# S140039_EMS_3HP_DS.net
KiCad netlist of a schematic drawn in EAGLE
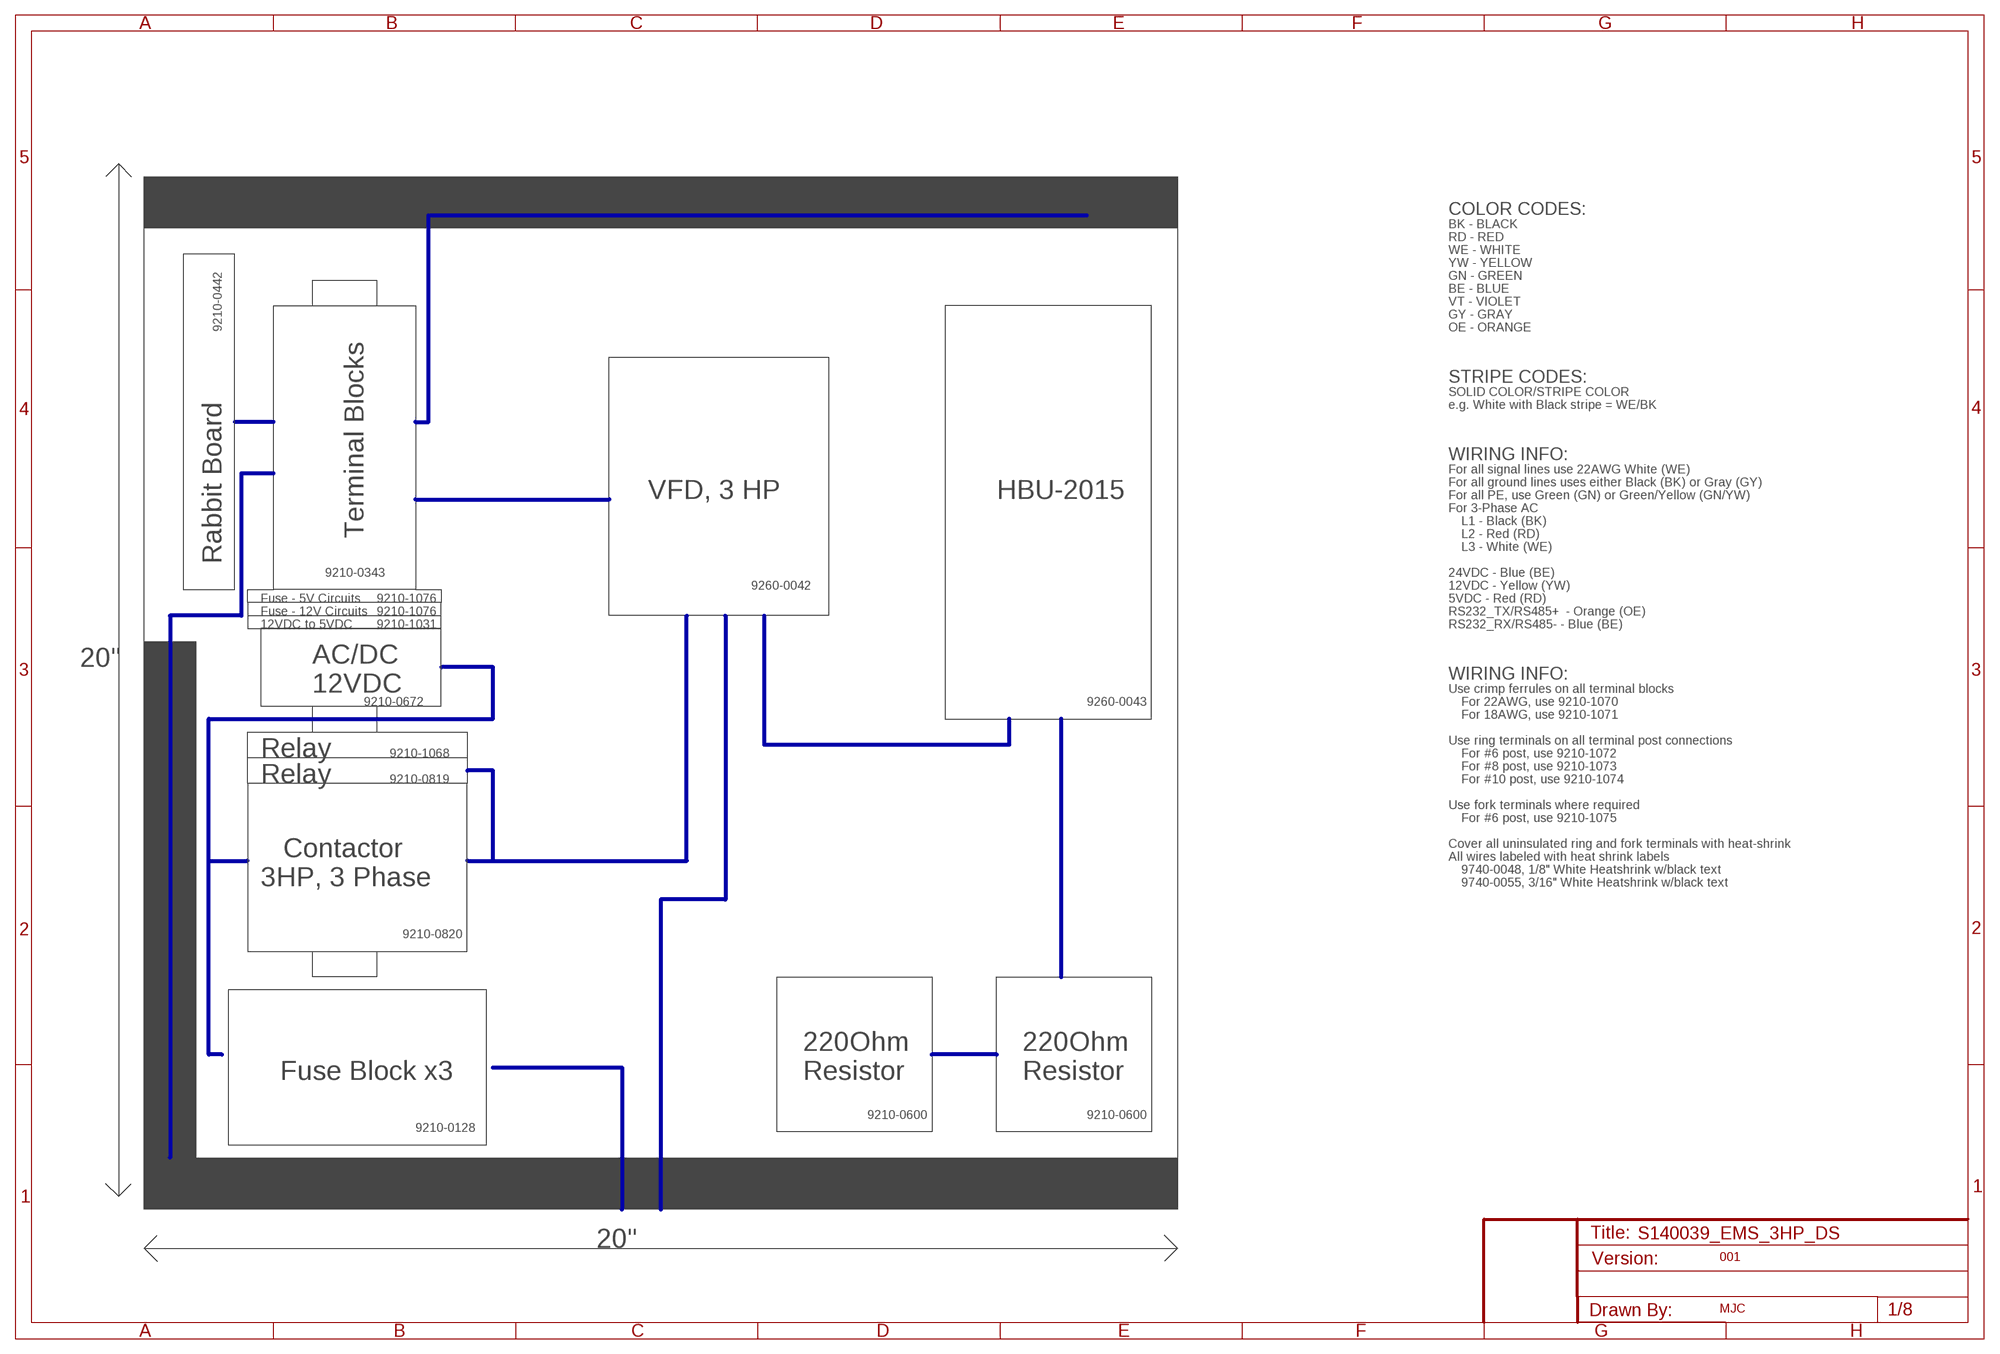
[diagram p0: schematic, sheet 1]
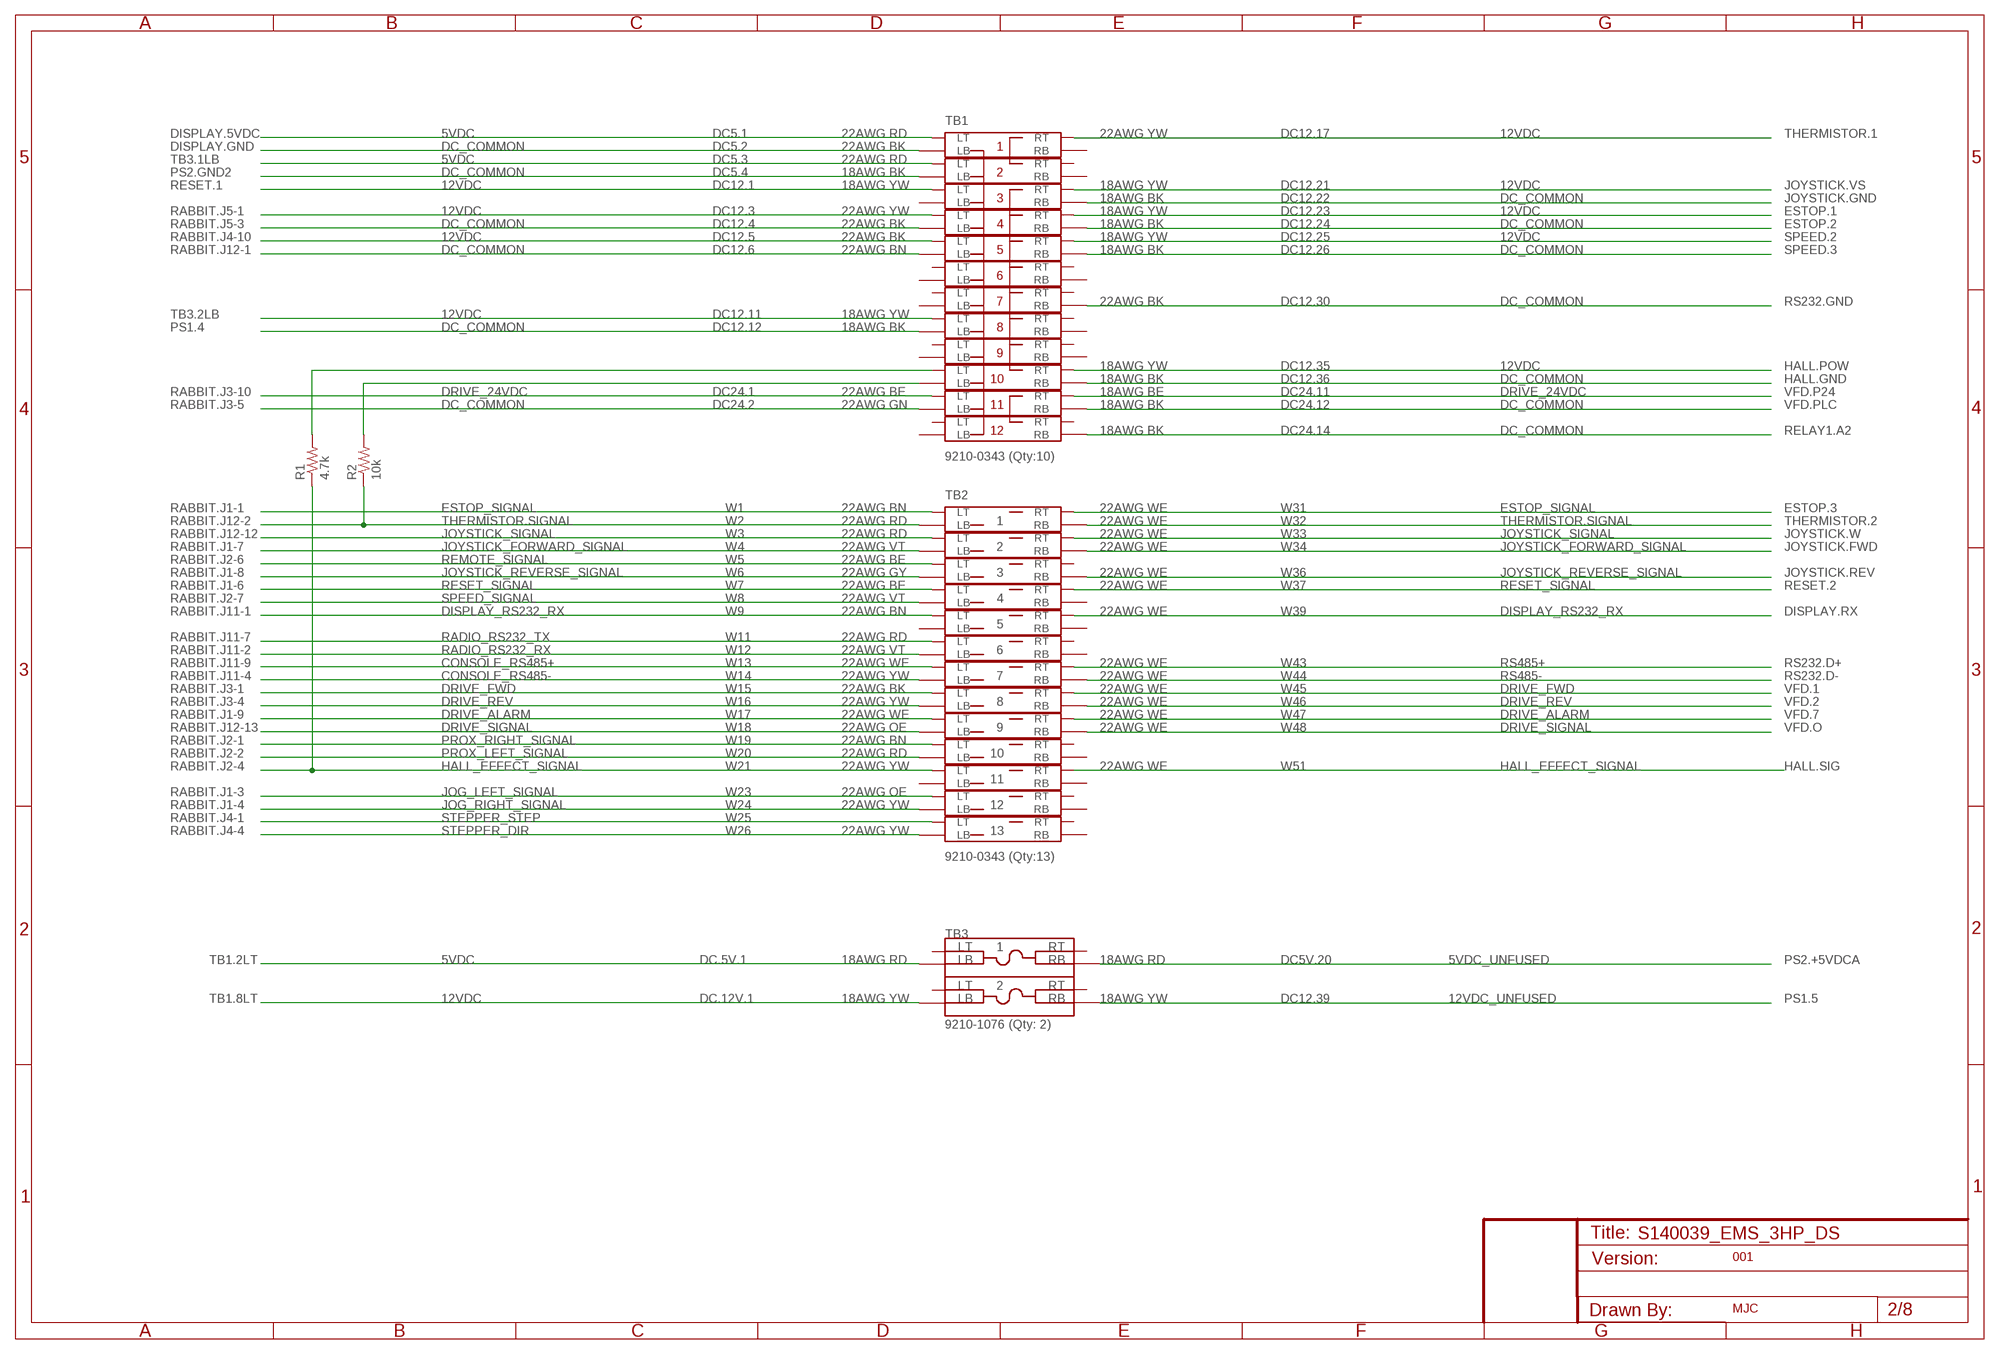
[diagram p1: schematic, sheet 2]
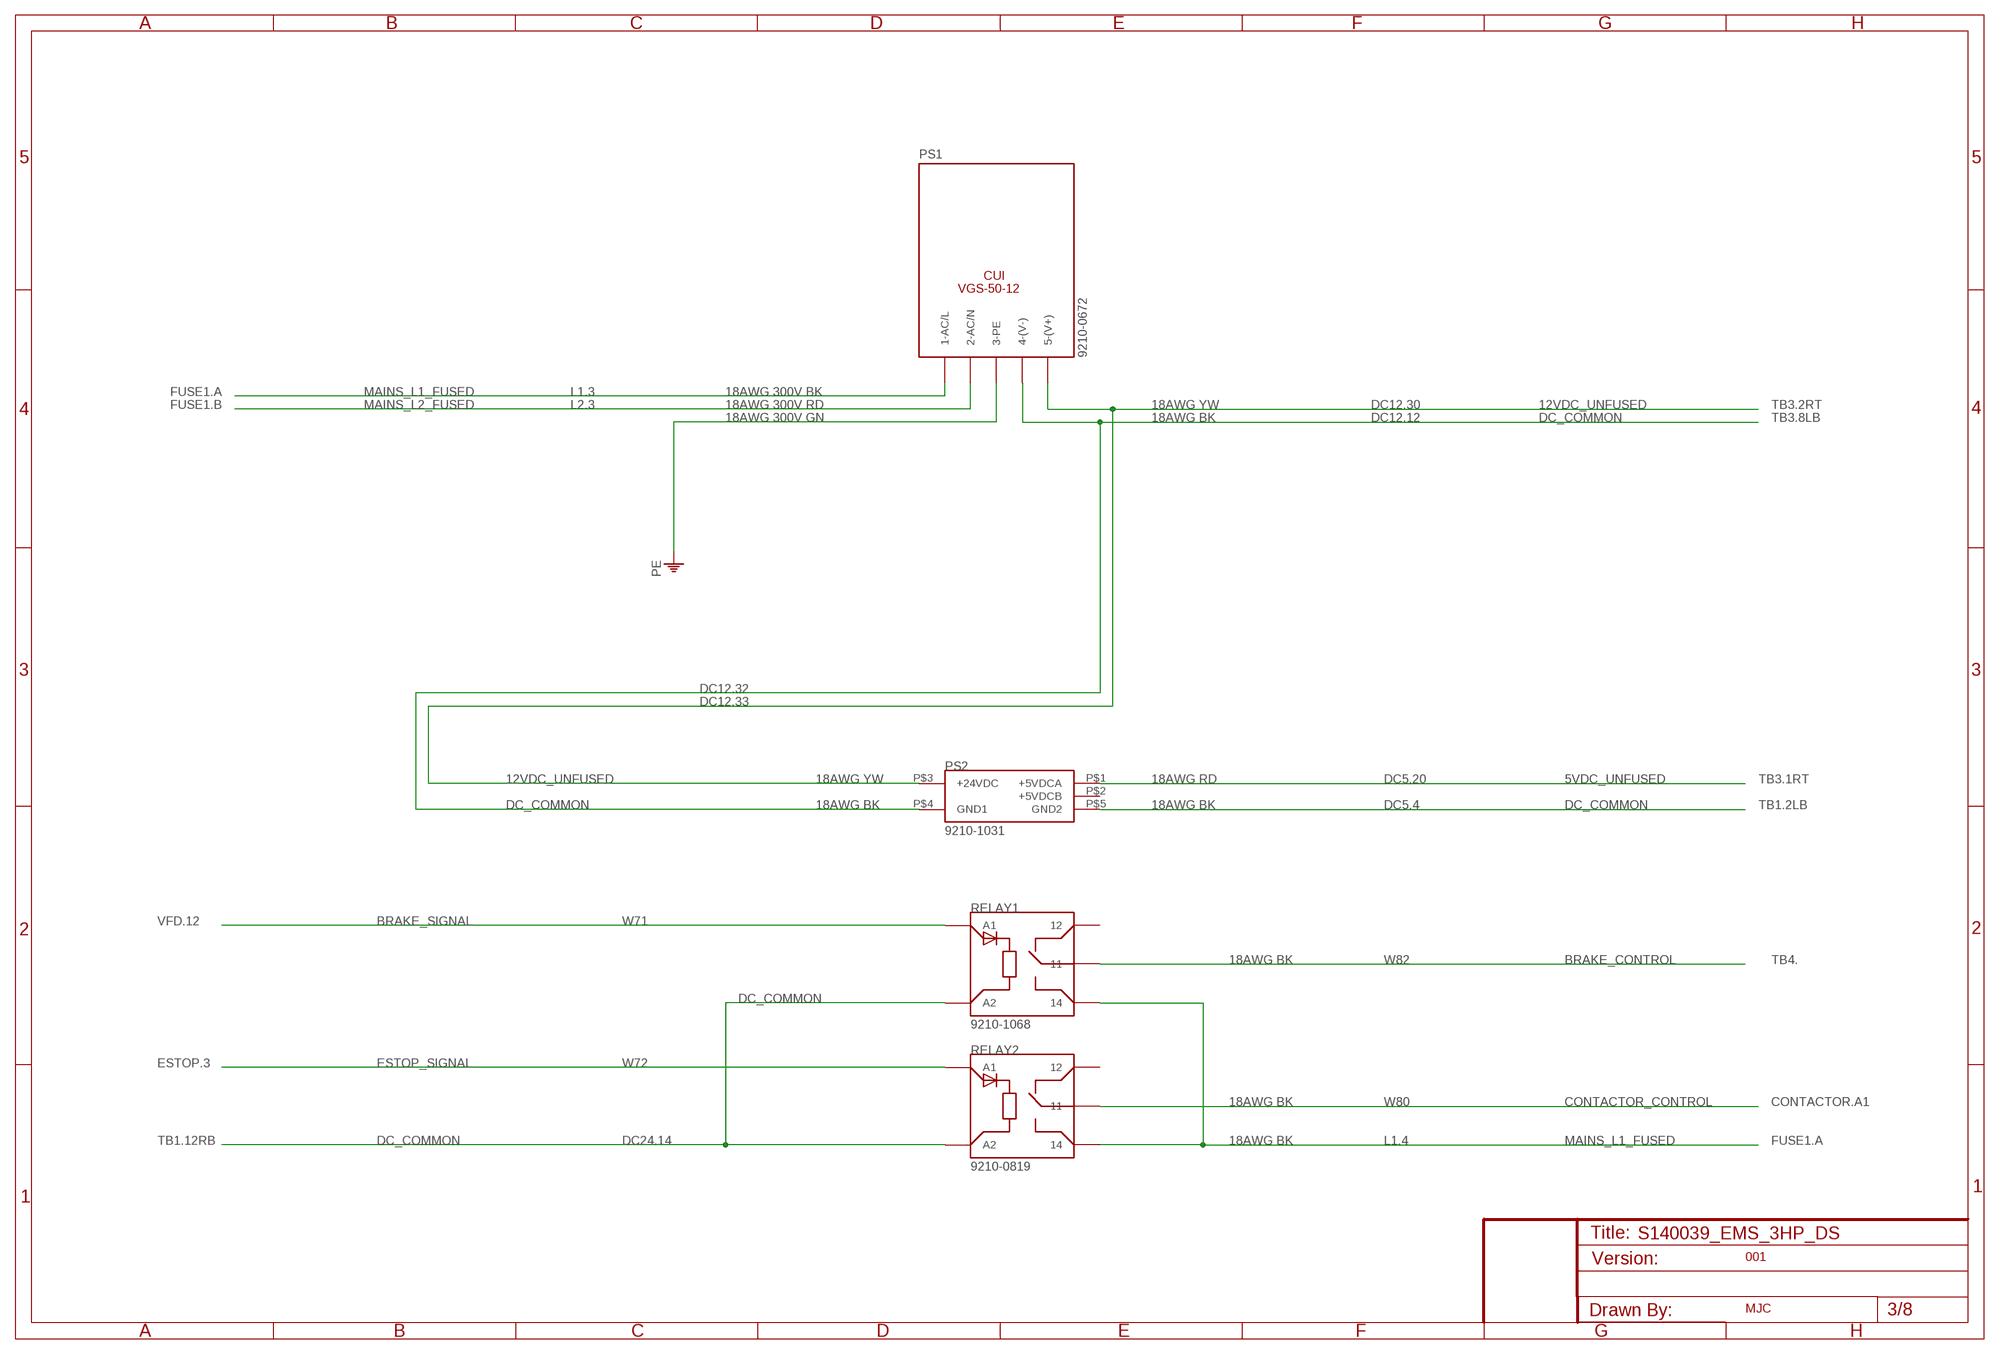
[diagram p2: schematic, sheet 3]
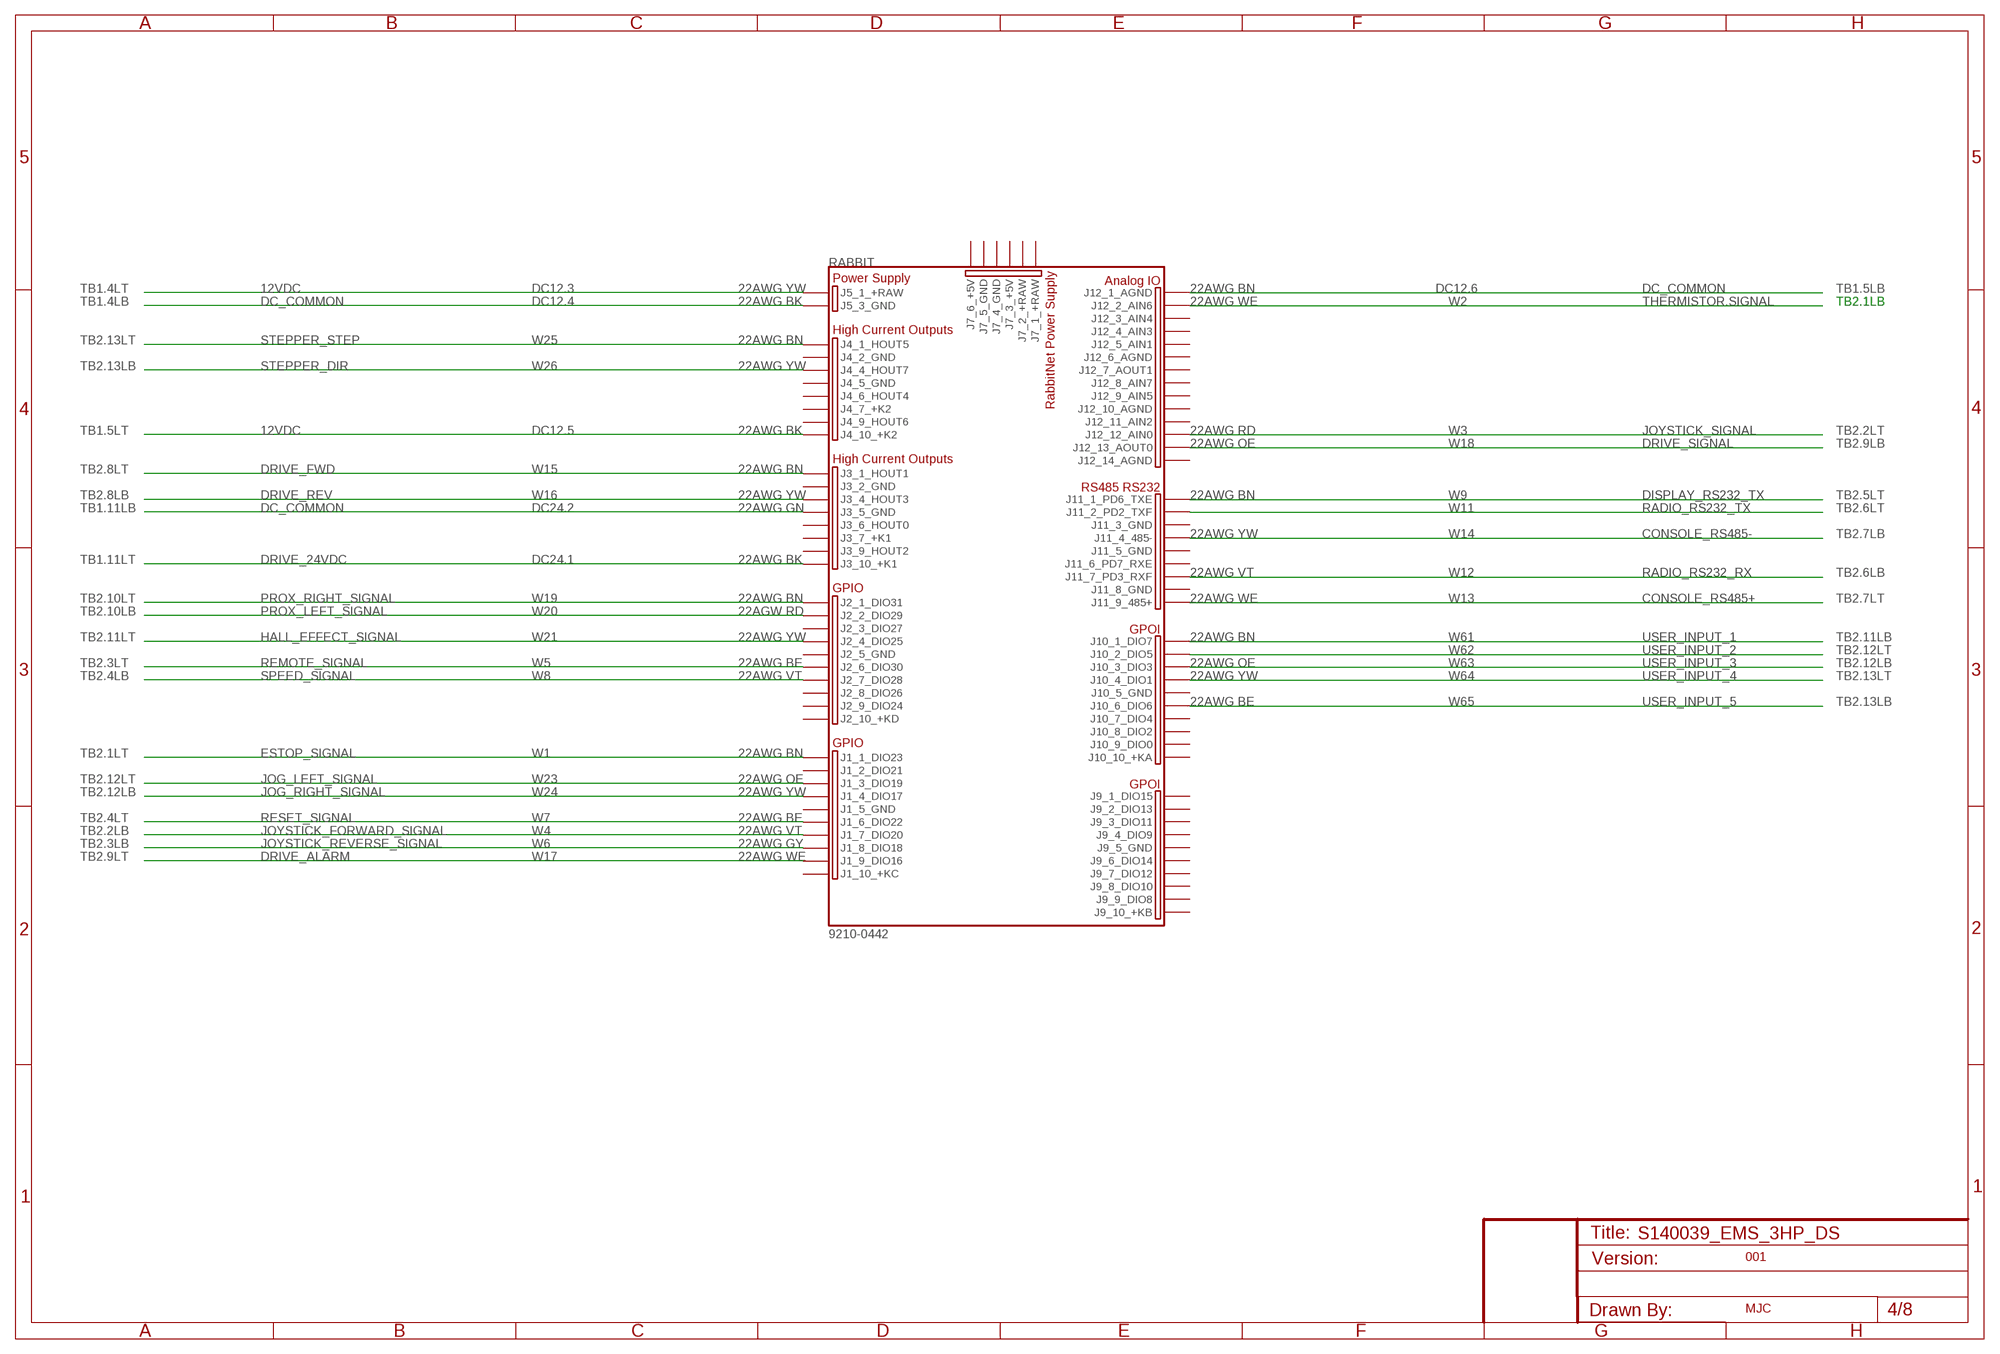
[diagram p3: schematic, sheet 4]
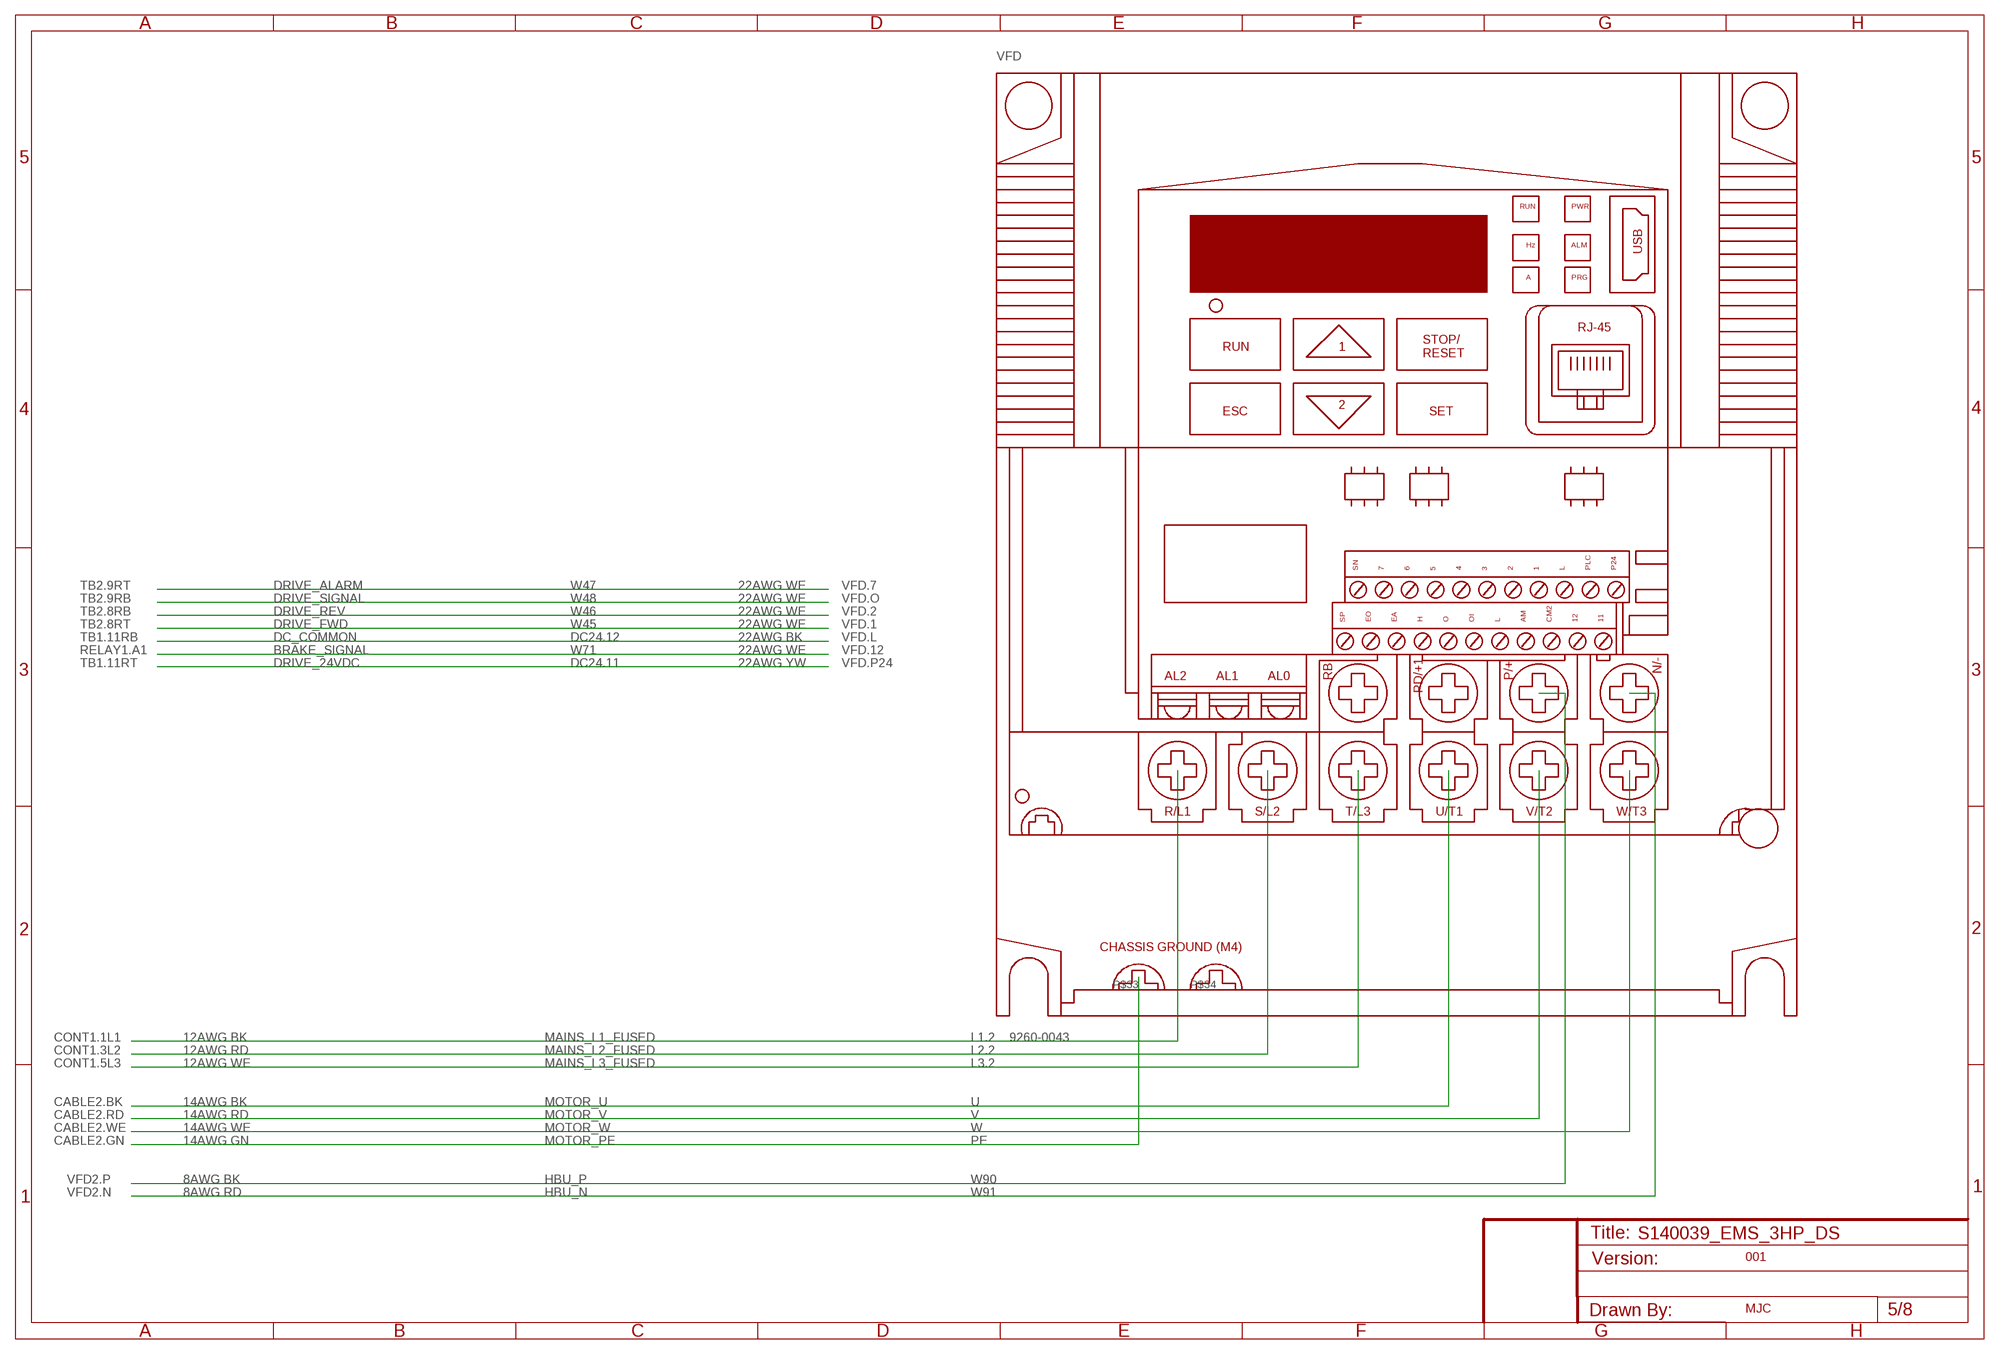
[diagram p4: schematic, sheet 5]
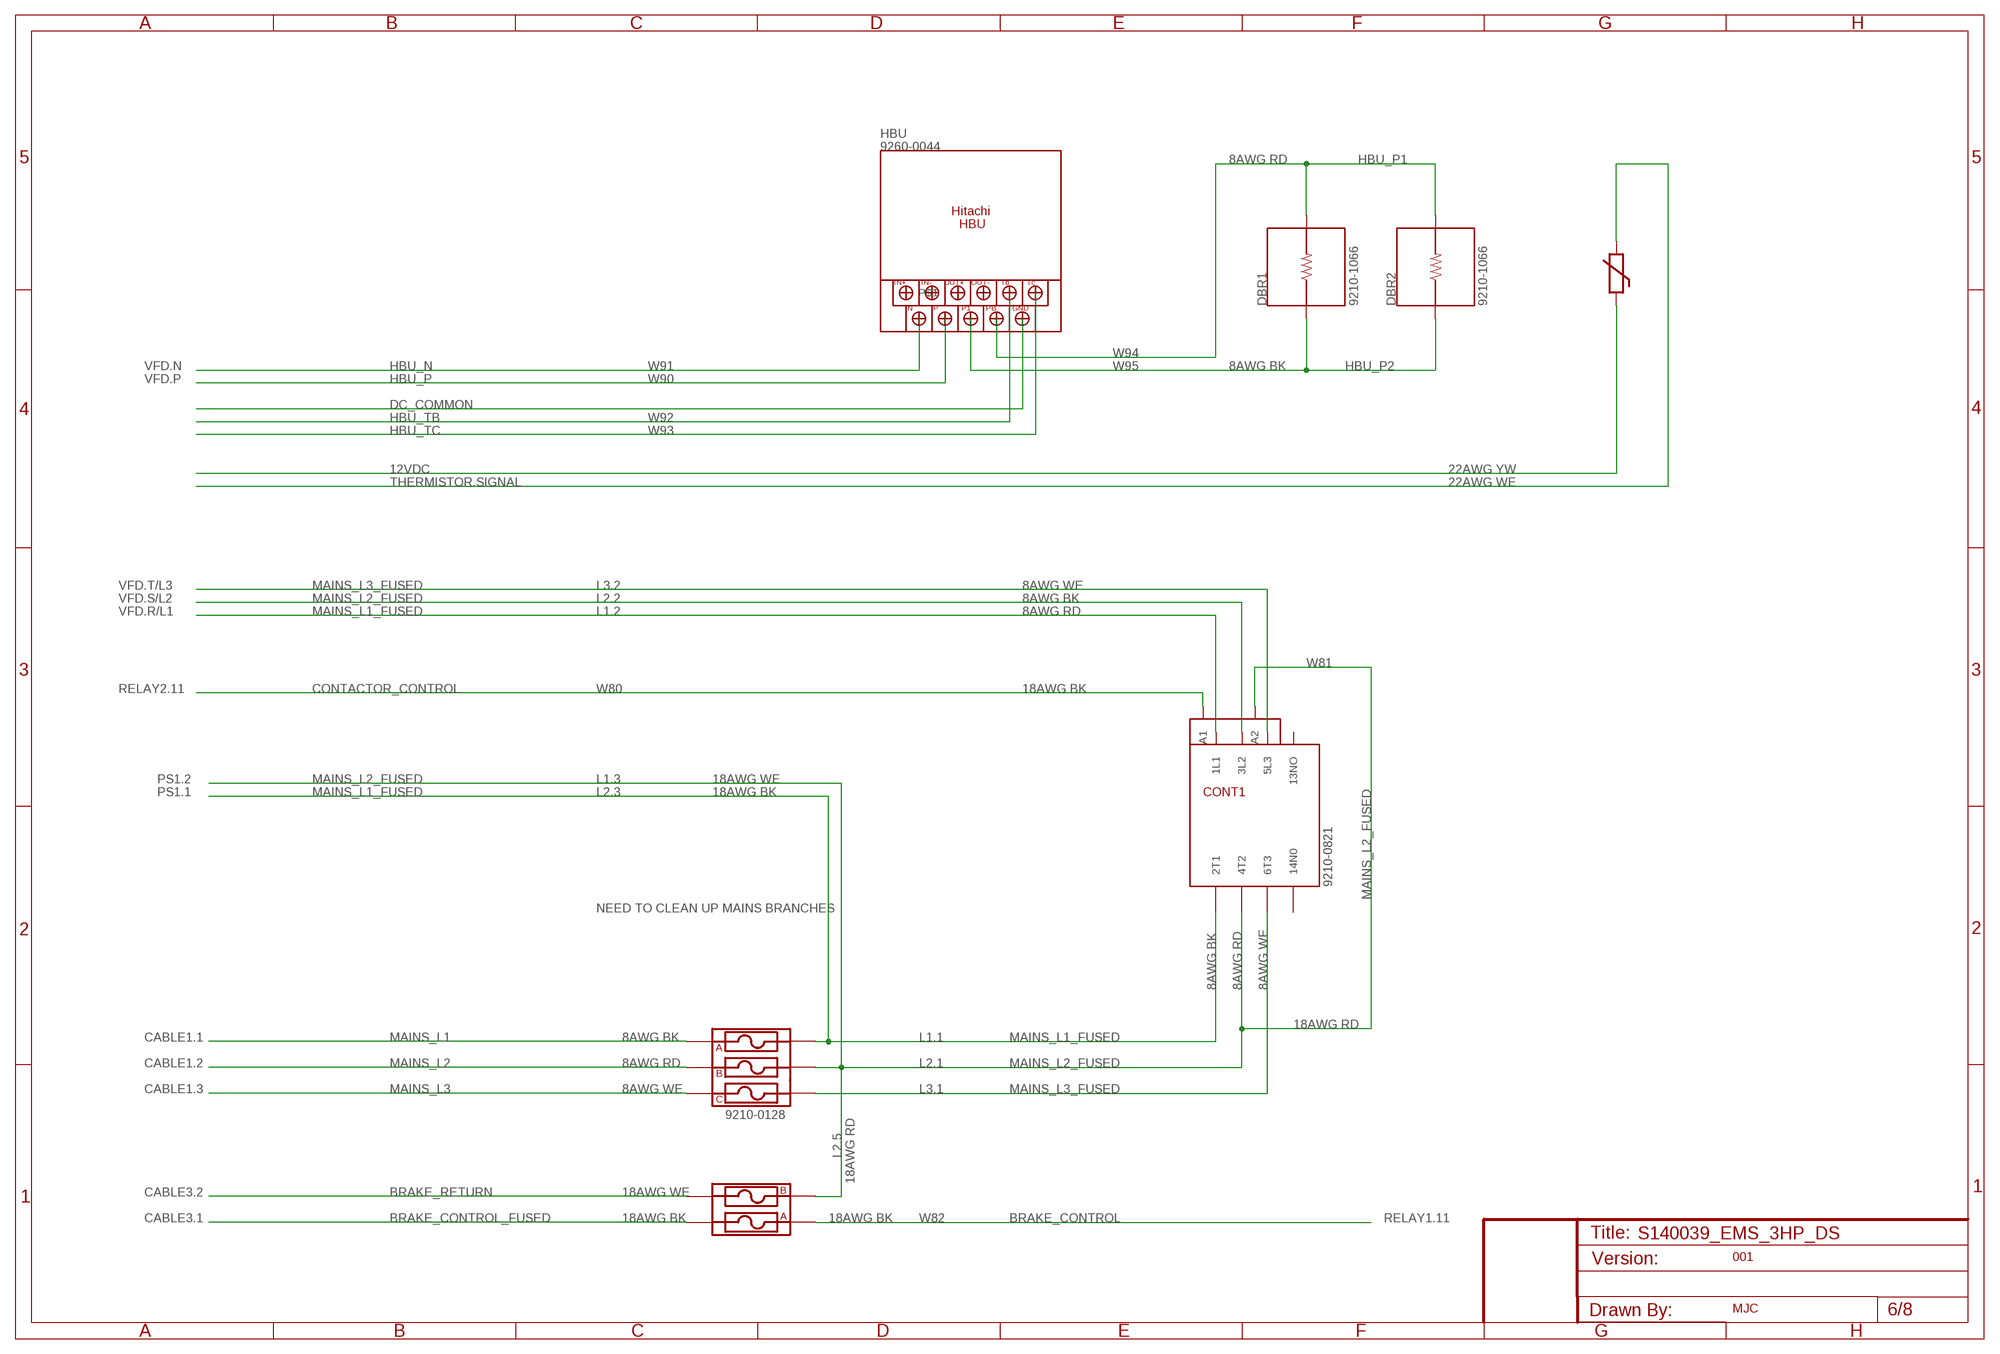
[diagram p5: schematic, sheet 6]
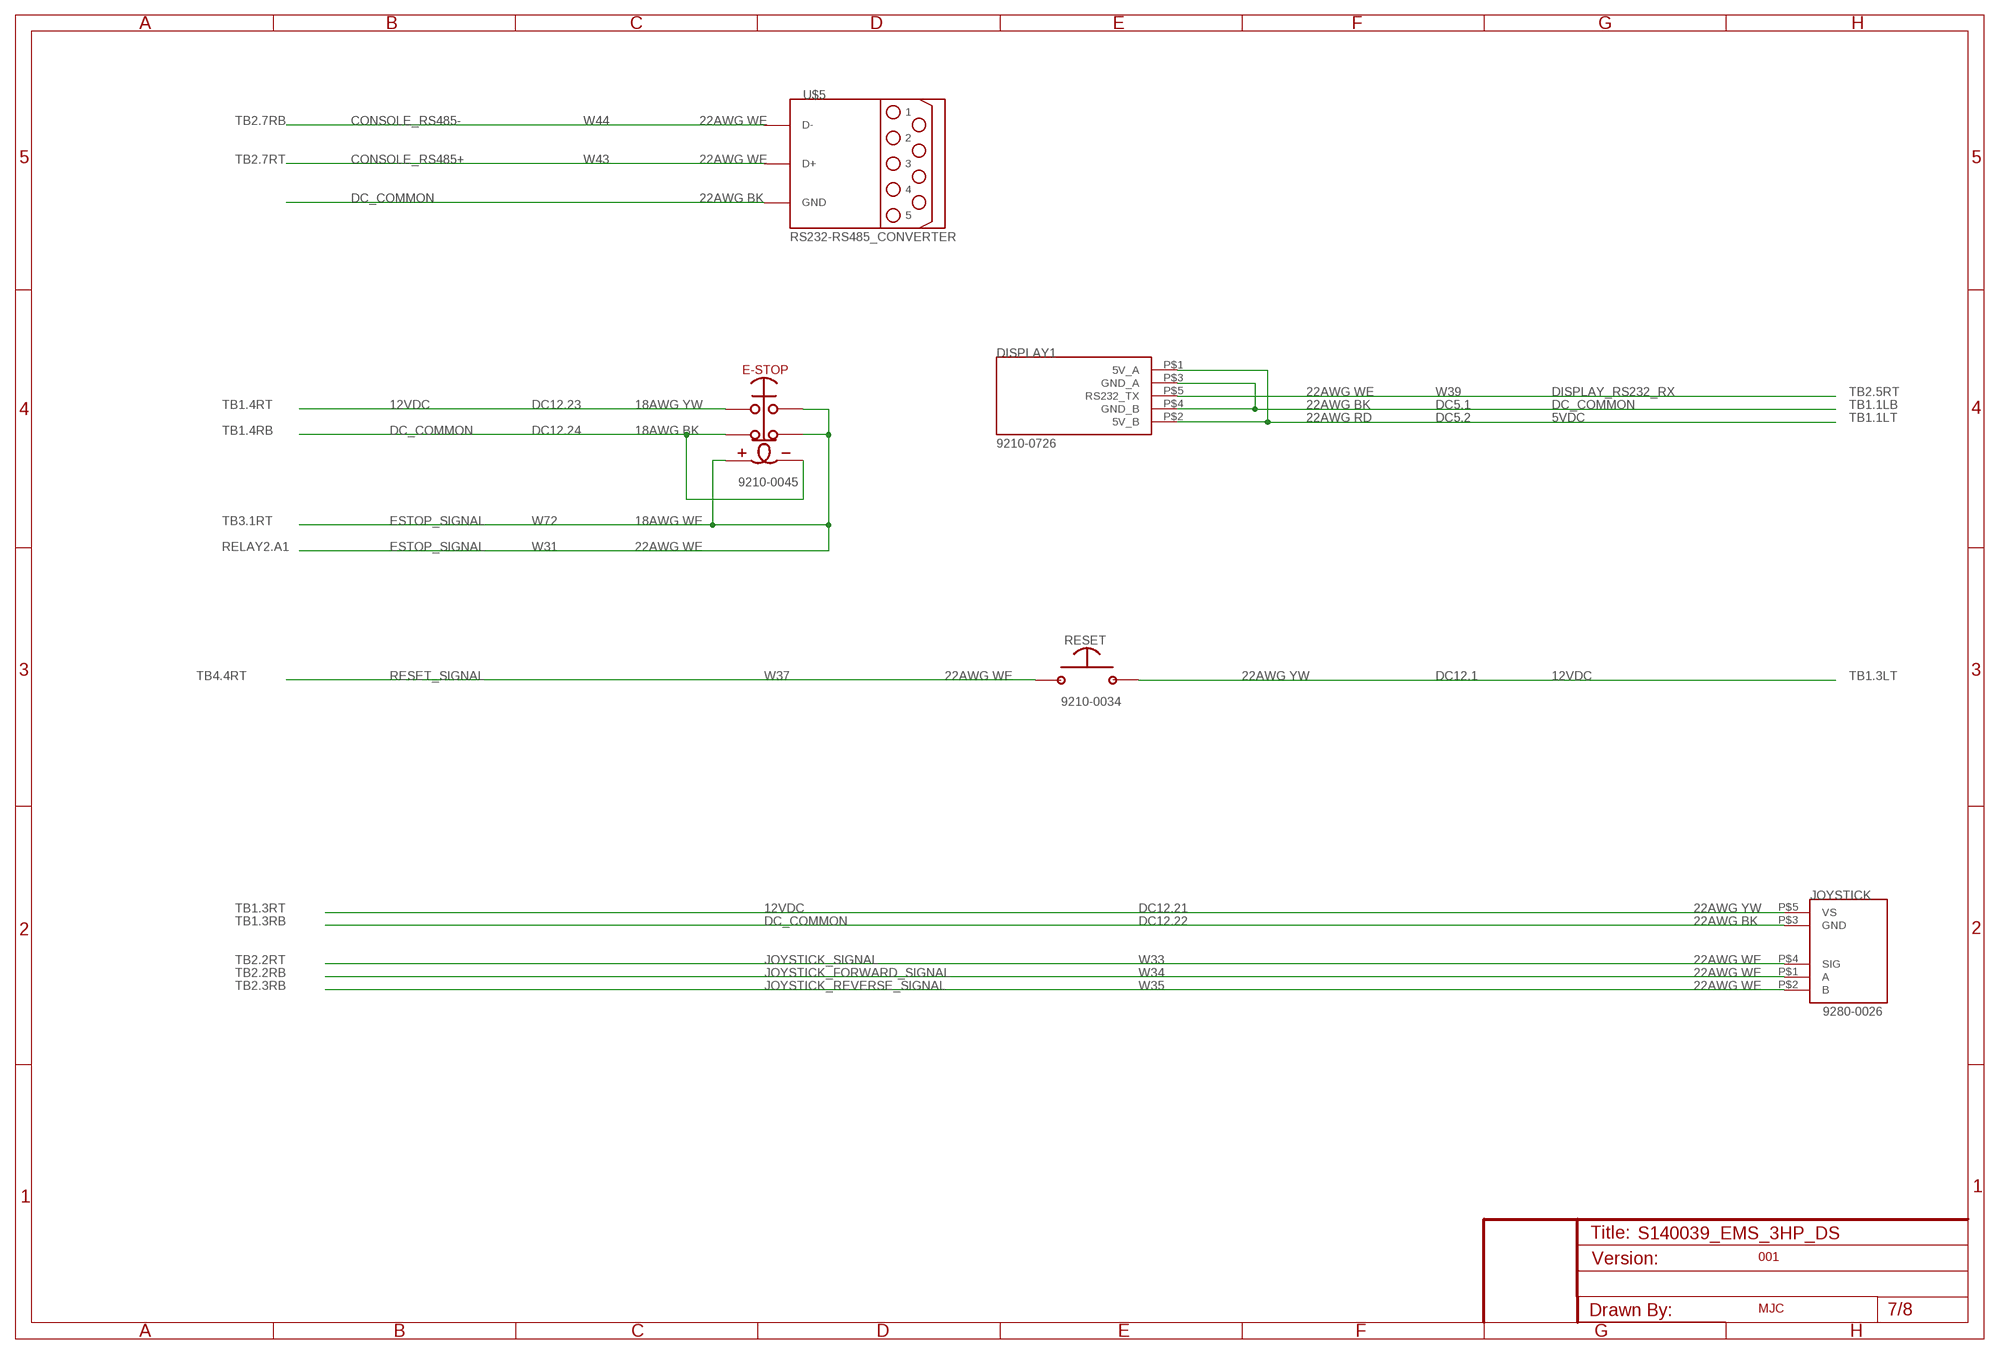
[diagram p6: schematic, sheet 7]
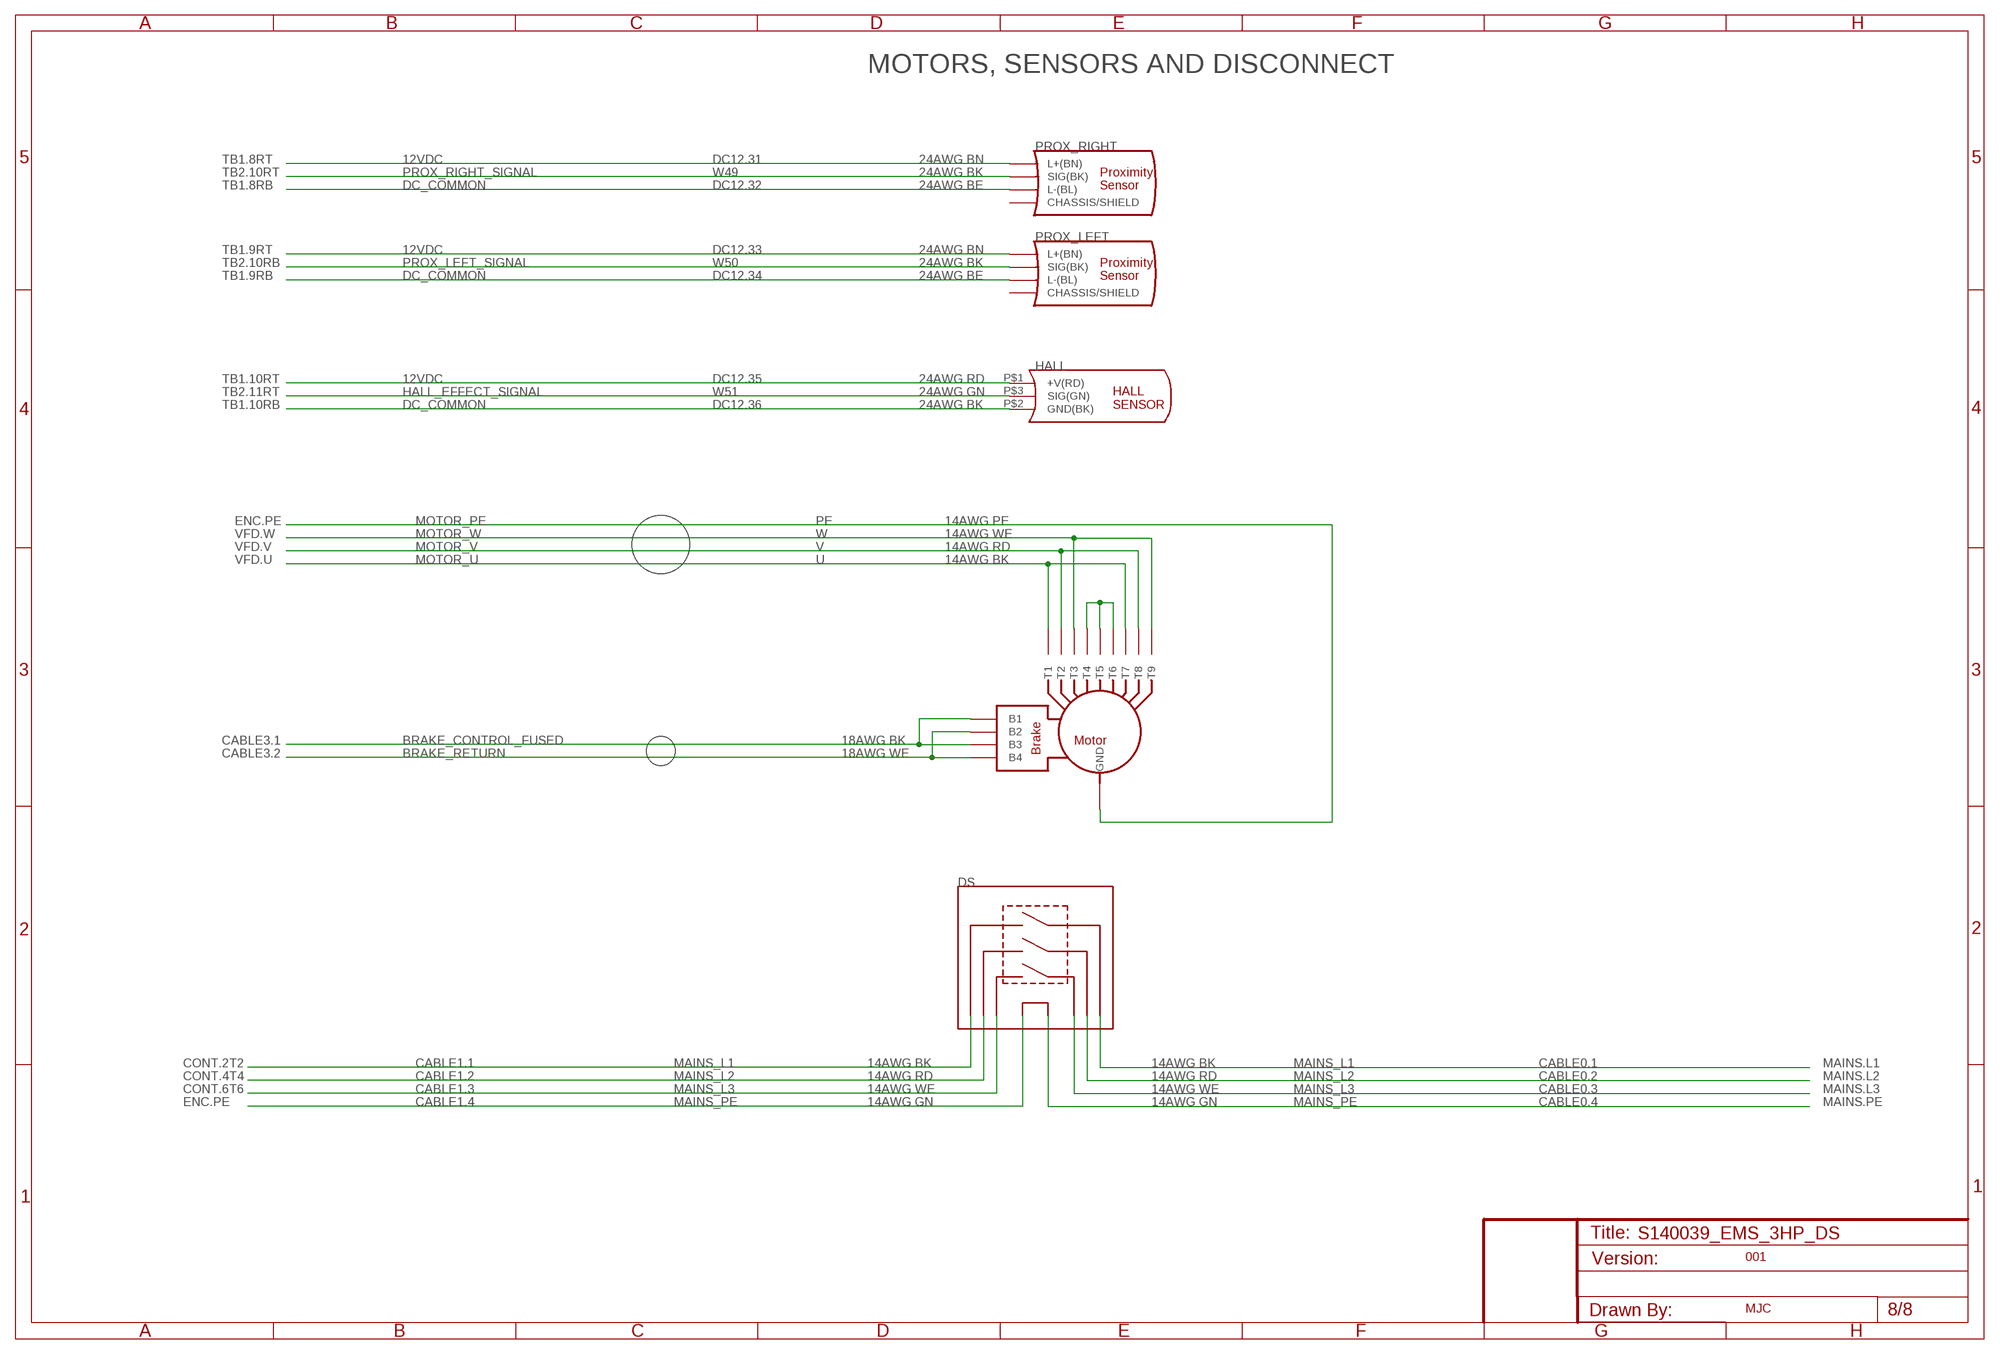
[diagram p7: schematic, sheet 8]

(export (version "E")
  (design (tool "Eeschema 10.0.6"))
  (components
    (comp (ref "CONT1")
      (value "CONTACTOR_3PHASE")
      (footprint "eagle-import:BOGUS")
      (libsource (lib "eagle-import") (part "CONTACTOR_3PHASE"))
    )
    (comp (ref "DBR1")
      (value "100 Ohm")
      (footprint "eagle-import:0204_5")
      (libsource (lib "eagle-import") (part "R-DYNAMIC_BRAKE"))
    )
    (comp (ref "DBR2")
      (value "100 Ohm")
      (footprint "eagle-import:0204_5")
      (libsource (lib "eagle-import") (part "R-DYNAMIC_BRAKE"))
    )
    (comp (ref "FUSE1")
      (value "FUSE_HOLDER_3-POLE")
      (footprint "eagle-import:BOGUS")
      (libsource (lib "eagle-import") (part "FUSE_HOLDER_3-POLE"))
    )
    (comp (ref "HBU")
      (value "HITACHI_HBU-2030")
      (footprint "eagle-import:BOGUS")
      (libsource (lib "eagle-import") (part "HITACHI_HBU-2030"))
    )
    (comp (ref "U$6")
      (value "FUSE_HOLDER_2-POLE")
      (footprint "eagle-import:BOGUS")
      (libsource (lib "eagle-import") (part "FUSE_HOLDER_2-POLE"))
    )
    (comp (ref "U$14")
      (value "THERMISTOR")
      (footprint "eagle-import:BOGUS")
      (libsource (lib "eagle-import") (part "THERMISTOR"))
    )
    (comp (ref "R1")
      (value "4.7k")
      (footprint "eagle-import:0204_5")
      (libsource (lib "eagle-import") (part "R-US_0204/5"))
    )
    (comp (ref "R2")
      (value "10k")
      (footprint "eagle-import:0204_5")
      (libsource (lib "eagle-import") (part "R-US_0204/5"))
    )
    (comp (ref "U$1")
      (value "TB_3031160_1POS")
      (footprint "eagle-import:BOGUS")
      (libsource (lib "eagle-import") (part "TB_3031160_1POS"))
    )
    (comp (ref "U$2")
      (value "TB_3031160_1POS")
      (footprint "eagle-import:BOGUS")
      (libsource (lib "eagle-import") (part "TB_3031160_1POS"))
    )
    (comp (ref "U$4")
      (value "TB_3031160_1POS")
      (footprint "eagle-import:BOGUS")
      (libsource (lib "eagle-import") (part "TB_3031160_1POS"))
    )
    (comp (ref "U$7")
      (value "TB_3031160_1POS")
      (footprint "eagle-import:BOGUS")
      (libsource (lib "eagle-import") (part "TB_3031160_1POS"))
    )
    (comp (ref "U$8")
      (value "TB_3031160_1POS")
      (footprint "eagle-import:BOGUS")
      (libsource (lib "eagle-import") (part "TB_3031160_1POS"))
    )
    (comp (ref "U$9")
      (value "TB_FUSE_DDFL4ULR")
      (footprint "eagle-import:BOGUS")
      (libsource (lib "eagle-import") (part "TB_FUSE_DDFL4ULR"))
    )
    (comp (ref "U$10")
      (value "TB_FUSE_DDFL4ULR")
      (footprint "eagle-import:BOGUS")
      (libsource (lib "eagle-import") (part "TB_FUSE_DDFL4ULR"))
    )
    (comp (ref "U$16")
      (value "TB_3031160_1POS")
      (footprint "eagle-import:BOGUS")
      (libsource (lib "eagle-import") (part "TB_3031160_1POS"))
    )
    (comp (ref "U$17")
      (value "TB_3031160_1POS")
      (footprint "eagle-import:BOGUS")
      (libsource (lib "eagle-import") (part "TB_3031160_1POS"))
    )
    (comp (ref "U$18")
      (value "TB_3031160_1POS")
      (footprint "eagle-import:BOGUS")
      (libsource (lib "eagle-import") (part "TB_3031160_1POS"))
    )
    (comp (ref "U$19")
      (value "TB_3031160_1POS")
      (footprint "eagle-import:BOGUS")
      (libsource (lib "eagle-import") (part "TB_3031160_1POS"))
    )
    (comp (ref "U$20")
      (value "TB_3031160_1POS")
      (footprint "eagle-import:BOGUS")
      (libsource (lib "eagle-import") (part "TB_3031160_1POS"))
    )
    (comp (ref "U$21")
      (value "TB_3031160_1POS")
      (footprint "eagle-import:BOGUS")
      (libsource (lib "eagle-import") (part "TB_3031160_1POS"))
    )
    (comp (ref "U$22")
      (value "TB_3031160_1POS")
      (footprint "eagle-import:BOGUS")
      (libsource (lib "eagle-import") (part "TB_3031160_1POS"))
    )
    (comp (ref "U$23")
      (value "TB_3031160_1POS")
      (footprint "eagle-import:BOGUS")
      (libsource (lib "eagle-import") (part "TB_3031160_1POS"))
    )
    (comp (ref "U$24")
      (value "TB_3031160_1POS")
      (footprint "eagle-import:BOGUS")
      (libsource (lib "eagle-import") (part "TB_3031160_1POS"))
    )
    (comp (ref "U$25")
      (value "TB_3031160_1POS")
      (footprint "eagle-import:BOGUS")
      (libsource (lib "eagle-import") (part "TB_3031160_1POS"))
    )
    (comp (ref "U$26")
      (value "TB_3031160_1POS")
      (footprint "eagle-import:BOGUS")
      (libsource (lib "eagle-import") (part "TB_3031160_1POS"))
    )
    (comp (ref "U$27")
      (value "TB_3031160_1POS")
      (footprint "eagle-import:BOGUS")
      (libsource (lib "eagle-import") (part "TB_3031160_1POS"))
    )
    (comp (ref "U$28")
      (value "TB_3031160_1POS")
      (footprint "eagle-import:BOGUS")
      (libsource (lib "eagle-import") (part "TB_3031160_1POS"))
    )
    (comp (ref "U$29")
      (value "TB_3031160_1POS")
      (footprint "eagle-import:BOGUS")
      (libsource (lib "eagle-import") (part "TB_3031160_1POS"))
    )
    (comp (ref "U$30")
      (value "TB_3031160_1POS")
      (footprint "eagle-import:BOGUS")
      (libsource (lib "eagle-import") (part "TB_3031160_1POS"))
    )
    (comp (ref "U$31")
      (value "TB_3031160_1POS")
      (footprint "eagle-import:BOGUS")
      (libsource (lib "eagle-import") (part "TB_3031160_1POS"))
    )
    (comp (ref "U$32")
      (value "TB_3031160_1POS")
      (footprint "eagle-import:BOGUS")
      (libsource (lib "eagle-import") (part "TB_3031160_1POS"))
    )
    (comp (ref "U$33")
      (value "TB_3031160_1POS")
      (footprint "eagle-import:BOGUS")
      (libsource (lib "eagle-import") (part "TB_3031160_1POS"))
    )
    (comp (ref "U$34")
      (value "TB_3031160_1POS")
      (footprint "eagle-import:BOGUS")
      (libsource (lib "eagle-import") (part "TB_3031160_1POS"))
    )
    (comp (ref "U$35")
      (value "TB_3031160_1POS")
      (footprint "eagle-import:BOGUS")
      (libsource (lib "eagle-import") (part "TB_3031160_1POS"))
    )
    (comp (ref "VFD")
      (value "HITACHI_WJ200-022LF")
      (footprint "eagle-import:BOGUS")
      (libsource (lib "eagle-import") (part "HITACHI_WJ200-022LF"))
    )
    (comp (ref "CPU1")
      (value "RABBIT_BL4S200(RCM4310)")
      (footprint "eagle-import:RABBIT_BL4S200")
      (libsource (lib "eagle-import") (part "RABBIT_BL4S200(RCM4310)"))
    )
    (comp (ref "DS")
      (value "DISCONNECT_SWITCH")
      (footprint "eagle-import:BOGUS")
      (libsource (lib "eagle-import") (part "DISCONNECT_SWITCH"))
    )
    (comp (ref "HALL")
      (value "DRUM_SENSOR")
      (footprint "eagle-import:BOGUS")
      (libsource (lib "eagle-import") (part "DRUM_SENSOR"))
    )
    (comp (ref "U$11")
      (value "MOTOR_3PH")
      (footprint "eagle-import:BOGUS")
      (libsource (lib "eagle-import") (part "MOTOR_3PH"))
    )
    (comp (ref "U$12")
      (value "SENSOR_PROXIMITY")
      (footprint "eagle-import:BOGUS")
      (libsource (lib "eagle-import") (part "SENSOR_PROXIMITY"))
    )
    (comp (ref "U$13")
      (value "SENSOR_PROXIMITY")
      (footprint "eagle-import:BOGUS")
      (libsource (lib "eagle-import") (part "SENSOR_PROXIMITY"))
    )
    (comp (ref "DISPLAY1")
      (value "SEETRON_GLO-416")
      (footprint "eagle-import:BOGUS")
      (libsource (lib "eagle-import") (part "SEETRON_GLO-416"))
    )
    (comp (ref "JOYSTICK")
      (value "JOYSTICK")
      (footprint "eagle-import:BOGUS")
      (libsource (lib "eagle-import") (part "JOYSTICK"))
    )
    (comp (ref "RESET")
      (value "SWITCH_MOM_NO")
      (footprint "eagle-import:BOGUS")
      (libsource (lib "eagle-import") (part "SWITCH_MOM_NO"))
    )
    (comp (ref "U$3")
      (value "SWITCH_ESTOP_LIGHTED")
      (footprint "eagle-import:BOGUS")
      (libsource (lib "eagle-import") (part "SWITCH_ESTOP_LIGHTED"))
    )
    (comp (ref "U$5")
      (value "RS232-RS485_CONVERTER")
      (footprint "eagle-import:BOGUS")
      (libsource (lib "eagle-import") (part "RS232-RS485_CONVERTER"))
    )
    (comp (ref "PS1")
      (value "DC-DC_CONVERTER_VGS-50-12")
      (footprint "eagle-import:BOGUS")
      (libsource (lib "eagle-import") (part "DC-DC_CONVERTER_VGS-50-12"))
    )
    (comp (ref "PS2")
      (value "DC-DC_CONVERTER_24V-5V")
      (footprint "eagle-import:BOGUS")
      (libsource (lib "eagle-import") (part "DC-DC_CONVERTER_24V-5V"))
    )
    (comp (ref "RELAY1")
      (value "RELAY_TB")
      (footprint "eagle-import:BOGUS")
      (libsource (lib "eagle-import") (part "RELAY_TB"))
    )
    (comp (ref "RELAY2")
      (value "RELAY_TB")
      (footprint "eagle-import:BOGUS")
      (libsource (lib "eagle-import") (part "RELAY_TB"))
    )
  )
  (nets
    (net (code "1") (name "5VDC") (class "Default")
      (node (ref "DISPLAY1") (pin "P$1") (pinfunction "5V_A_P$1") (pintype "bidirectional"))
      (node (ref "DISPLAY1") (pin "P$2") (pinfunction "5V_B_P$2") (pintype "bidirectional"))
      (node (ref "U$34") (pin "P$2") (pinfunction "LT_P$2") (pintype "bidirectional"))
      (node (ref "U$35") (pin "P$2") (pinfunction "LT_P$2") (pintype "bidirectional"))
      (node (ref "U$9") (pin "P$2") (pinfunction "P$2_P$2") (pintype "bidirectional"))
    )
    (net (code "2") (name "5VDC_UNFUSED") (class "Default")
      (node (ref "PS2") (pin "P$1") (pinfunction "+5VDCA_P$1") (pintype "bidirectional"))
      (node (ref "U$9") (pin "P$4") (pinfunction "P$4_P$4") (pintype "bidirectional"))
    )
    (net (code "3") (name "12VDC") (class "Default")
      (node (ref "CPU1") (pin "P$J4-10") (pinfunction "J4_10_+K2_P$J4-10") (pintype "bidirectional"))
      (node (ref "CPU1") (pin "P$J5-1") (pinfunction "J5_1_+RAW_P$J5-1") (pintype "bidirectional"))
      (node (ref "HALL") (pin "P$1") (pinfunction "+V(RD)_P$1") (pintype "bidirectional"))
      (node (ref "JOYSTICK") (pin "P$5") (pinfunction "VS_P$5") (pintype "bidirectional"))
      (node (ref "RESET") (pin "P$2") (pinfunction "P$2_P$2") (pintype "bidirectional"))
      (node (ref "U$10") (pin "P$2") (pinfunction "P$2_P$2") (pintype "bidirectional"))
      (node (ref "U$12") (pin "P$2") (pinfunction "L+(BN)_P$2") (pintype "bidirectional"))
      (node (ref "U$13") (pin "P$2") (pinfunction "L+(BN)_P$2") (pintype "bidirectional"))
      (node (ref "U$14") (pin "P$2") (pinfunction "P$2_P$2") (pintype "bidirectional"))
      (node (ref "U$28") (pin "P$2") (pinfunction "LT_P$2") (pintype "bidirectional"))
      (node (ref "U$3") (pin "P$1") (pinfunction "P$1_P$1") (pintype "bidirectional"))
      (node (ref "U$31") (pin "P$2") (pinfunction "LT_P$2") (pintype "bidirectional"))
      (node (ref "U$31") (pin "P$4") (pinfunction "RT_P$4") (pintype "bidirectional"))
      (node (ref "U$32") (pin "P$2") (pinfunction "LT_P$2") (pintype "bidirectional"))
      (node (ref "U$32") (pin "P$4") (pinfunction "RT_P$4") (pintype "bidirectional"))
      (node (ref "U$33") (pin "P$2") (pinfunction "LT_P$2") (pintype "bidirectional"))
      (node (ref "U$33") (pin "P$4") (pinfunction "RT_P$4") (pintype "bidirectional"))
      (node (ref "U$35") (pin "P$4") (pinfunction "RT_P$4") (pintype "bidirectional"))
      (node (ref "U$8") (pin "P$4") (pinfunction "RT_P$4") (pintype "bidirectional"))
    )
    (net (code "4") (name "12VDC_UNFUSED") (class "Default")
      (node (ref "PS1") (pin "P$5") (pinfunction "5-(V+)_P$5") (pintype "bidirectional"))
      (node (ref "PS2") (pin "P$3") (pinfunction "+24VDC_P$3") (pintype "bidirectional"))
      (node (ref "U$10") (pin "P$4") (pinfunction "P$4_P$4") (pintype "bidirectional"))
    )
    (net (code "5") (name "BRAKE_CONTROL") (class "Default")
      (node (ref "RELAY1") (pin "P$1") (pinfunction "11_P$1") (pintype "bidirectional"))
      (node (ref "U$6") (pin "P$2") (pinfunction "P$2_P$2") (pintype "bidirectional"))
    )
    (net (code "6") (name "BRAKE_CONTROL_FUSED") (class "Default")
      (node (ref "U$11") (pin "P$1") (pinfunction "B1_P$1") (pintype "bidirectional"))
      (node (ref "U$11") (pin "P$3") (pinfunction "B3_P$3") (pintype "bidirectional"))
      (node (ref "U$6") (pin "P$3") (pinfunction "P$3_P$3") (pintype "bidirectional"))
    )
    (net (code "7") (name "BRAKE_RETURN") (class "Default")
      (node (ref "U$11") (pin "P$2") (pinfunction "B2_P$2") (pintype "bidirectional"))
      (node (ref "U$11") (pin "P$4") (pinfunction "B4_P$4") (pintype "bidirectional"))
      (node (ref "U$6") (pin "P$4") (pinfunction "P$4_P$4") (pintype "bidirectional"))
    )
    (net (code "8") (name "BRAKE_SIGNAL") (class "Default")
      (node (ref "RELAY1") (pin "P$4") (pinfunction "A1_P$4") (pintype "bidirectional"))
    )
    (net (code "9") (name "CONSOLE_RS485+") (class "Default")
      (node (ref "CPU1") (pin "P$J11-9") (pinfunction "J11_9_485+_P$J11-9") (pintype "bidirectional"))
      (node (ref "U$21") (pin "P$2") (pinfunction "LT_P$2") (pintype "bidirectional"))
      (node (ref "U$5") (pin "P$10") (pinfunction "D+_P$10") (pintype "bidirectional"))
    )
    (net (code "10") (name "CONSOLE_RS485-") (class "Default")
      (node (ref "CPU1") (pin "P$J11-4") (pinfunction "J11_4_485-_P$J11-4") (pintype "bidirectional"))
      (node (ref "U$21") (pin "P$1") (pinfunction "LB_P$1") (pintype "bidirectional"))
      (node (ref "U$5") (pin "P$11") (pinfunction "D-_P$11") (pintype "bidirectional"))
    )
    (net (code "11") (name "CONTACTOR_CONTROL") (class "Default")
      (node (ref "CONT1") (pin "P$9") (pinfunction "A1_P$9") (pintype "bidirectional"))
      (node (ref "RELAY2") (pin "P$1") (pinfunction "11_P$1") (pintype "bidirectional"))
    )
    (net (code "12") (name "DC_COMMON") (class "Default")
      (node (ref "CPU1") (pin "P$J12-1") (pinfunction "J12_1_AGND_P$J12-1") (pintype "bidirectional"))
      (node (ref "CPU1") (pin "P$J3-5") (pinfunction "J3_5_GND_P$J3-5") (pintype "bidirectional"))
      (node (ref "CPU1") (pin "P$J5-3") (pinfunction "J5_3_GND_P$J5-3") (pintype "bidirectional"))
      (node (ref "DISPLAY1") (pin "P$3") (pinfunction "GND_A_P$3") (pintype "bidirectional"))
      (node (ref "DISPLAY1") (pin "P$4") (pinfunction "GND_B_P$4") (pintype "bidirectional"))
      (node (ref "HALL") (pin "P$2") (pinfunction "GND(BK)_P$2") (pintype "bidirectional"))
      (node (ref "HBU") (pin "P$7") (pinfunction "P$7_P$7") (pintype "bidirectional"))
      (node (ref "JOYSTICK") (pin "P$3") (pinfunction "GND_P$3") (pintype "bidirectional"))
      (node (ref "PS1") (pin "P$4") (pinfunction "4-(V-)_P$4") (pintype "bidirectional"))
      (node (ref "PS2") (pin "P$4") (pinfunction "GND1_P$4") (pintype "bidirectional"))
      (node (ref "PS2") (pin "P$5") (pinfunction "GND2_P$5") (pintype "bidirectional"))
      (node (ref "RELAY1") (pin "P$5") (pinfunction "A2_P$5") (pintype "bidirectional"))
      (node (ref "RELAY2") (pin "P$5") (pinfunction "A2_P$5") (pintype "bidirectional"))
      (node (ref "U$12") (pin "P$3") (pinfunction "L-(BL)_P$3") (pintype "bidirectional"))
      (node (ref "U$13") (pin "P$3") (pinfunction "L-(BL)_P$3") (pintype "bidirectional"))
      (node (ref "U$26") (pin "P$3") (pinfunction "RB_P$3") (pintype "bidirectional"))
      (node (ref "U$27") (pin "P$1") (pinfunction "LB_P$1") (pintype "bidirectional"))
      (node (ref "U$27") (pin "P$3") (pinfunction "RB_P$3") (pintype "bidirectional"))
      (node (ref "U$28") (pin "P$1") (pinfunction "LB_P$1") (pintype "bidirectional"))
      (node (ref "U$29") (pin "P$3") (pinfunction "RB_P$3") (pintype "bidirectional"))
      (node (ref "U$3") (pin "P$2") (pinfunction "P$2_P$2") (pintype "bidirectional"))
      (node (ref "U$3") (pin "P$6") (pinfunction "P$6_P$6") (pintype "bidirectional"))
      (node (ref "U$31") (pin "P$1") (pinfunction "LB_P$1") (pintype "bidirectional"))
      (node (ref "U$31") (pin "P$3") (pinfunction "RB_P$3") (pintype "bidirectional"))
      (node (ref "U$32") (pin "P$1") (pinfunction "LB_P$1") (pintype "bidirectional"))
      (node (ref "U$32") (pin "P$3") (pinfunction "RB_P$3") (pintype "bidirectional"))
      (node (ref "U$33") (pin "P$3") (pinfunction "RB_P$3") (pintype "bidirectional"))
      (node (ref "U$34") (pin "P$1") (pinfunction "LB_P$1") (pintype "bidirectional"))
      (node (ref "U$35") (pin "P$1") (pinfunction "LB_P$1") (pintype "bidirectional"))
      (node (ref "U$5") (pin "P$12") (pinfunction "GND_P$12") (pintype "bidirectional"))
      (node (ref "U$8") (pin "P$3") (pinfunction "RB_P$3") (pintype "bidirectional"))
    )
    (net (code "13") (name "DISPLAY_RS232_RX") (class "Default")
      (node (ref "DISPLAY1") (pin "P$5") (pinfunction "RS232_TX_P$5") (pintype "bidirectional"))
      (node (ref "U$19") (pin "P$2") (pinfunction "LT_P$2") (pintype "bidirectional"))
      (node (ref "U$19") (pin "P$4") (pinfunction "RT_P$4") (pintype "bidirectional"))
    )
    (net (code "14") (name "DISPLAY_RS232_TX") (class "Default")
      (node (ref "CPU1") (pin "P$J11-1") (pinfunction "J11_1_PD6_TXE_P$J11-1") (pintype "bidirectional"))
    )
    (net (code "15") (name "DRIVE_24VDC") (class "Default")
      (node (ref "CPU1") (pin "P$J3-10") (pinfunction "J3_10_+K1_P$J3-10") (pintype "bidirectional"))
      (node (ref "U$27") (pin "P$2") (pinfunction "LT_P$2") (pintype "bidirectional"))
      (node (ref "U$27") (pin "P$4") (pinfunction "RT_P$4") (pintype "bidirectional"))
    )
    (net (code "16") (name "DRIVE_ALARM") (class "Default")
      (node (ref "CPU1") (pin "P$J1-9") (pinfunction "J1_9_DIO16_P$J1-9") (pintype "bidirectional"))
      (node (ref "U$23") (pin "P$2") (pinfunction "LT_P$2") (pintype "bidirectional"))
      (node (ref "U$23") (pin "P$4") (pinfunction "RT_P$4") (pintype "bidirectional"))
    )
    (net (code "17") (name "DRIVE_FWD") (class "Default")
      (node (ref "CPU1") (pin "P$J3-1") (pinfunction "J3_1_HOUT1_P$J3-1") (pintype "bidirectional"))
      (node (ref "U$22") (pin "P$2") (pinfunction "LT_P$2") (pintype "bidirectional"))
      (node (ref "U$22") (pin "P$4") (pinfunction "RT_P$4") (pintype "bidirectional"))
    )
    (net (code "18") (name "DRIVE_REV") (class "Default")
      (node (ref "CPU1") (pin "P$J3-4") (pinfunction "J3_4_HOUT3_P$J3-4") (pintype "bidirectional"))
      (node (ref "U$22") (pin "P$1") (pinfunction "LB_P$1") (pintype "bidirectional"))
      (node (ref "U$22") (pin "P$3") (pinfunction "RB_P$3") (pintype "bidirectional"))
    )
    (net (code "19") (name "DRIVE_SIGNAL") (class "Default")
      (node (ref "CPU1") (pin "P$J12-13") (pinfunction "J12_13_AOUT0_P$J12-13") (pintype "bidirectional"))
      (node (ref "U$23") (pin "P$1") (pinfunction "LB_P$1") (pintype "bidirectional"))
      (node (ref "U$23") (pin "P$3") (pinfunction "RB_P$3") (pintype "bidirectional"))
    )
    (net (code "20") (name "ESTOP_SIGNAL") (class "Default")
      (node (ref "CPU1") (pin "P$J1-1") (pinfunction "J1_1_DIO23_P$J1-1") (pintype "bidirectional"))
      (node (ref "RELAY2") (pin "P$4") (pinfunction "A1_P$4") (pintype "bidirectional"))
      (node (ref "U$3") (pin "P$3") (pinfunction "P$3_P$3") (pintype "bidirectional"))
      (node (ref "U$3") (pin "P$4") (pinfunction "P$4_P$4") (pintype "bidirectional"))
      (node (ref "U$3") (pin "P$5") (pinfunction "P$5_P$5") (pintype "bidirectional"))
      (node (ref "U$4") (pin "P$2") (pinfunction "LT_P$2") (pintype "bidirectional"))
      (node (ref "U$4") (pin "P$4") (pinfunction "RT_P$4") (pintype "bidirectional"))
    )
    (net (code "21") (name "HALL_EFFECT_SIGNAL") (class "Default")
      (node (ref "CPU1") (pin "P$J2-4") (pinfunction "J2_4_DIO25_P$J2-4") (pintype "bidirectional"))
      (node (ref "HALL") (pin "P$3") (pinfunction "SIG(GN)_P$3") (pintype "bidirectional"))
      (node (ref "R1") (pin "1") (pinfunction "1_1") (pintype "passive"))
      (node (ref "U$25") (pin "P$2") (pinfunction "LT_P$2") (pintype "bidirectional"))
      (node (ref "U$25") (pin "P$4") (pinfunction "RT_P$4") (pintype "bidirectional"))
    )
    (net (code "22") (name "HBU_N") (class "Default")
      (node (ref "HBU") (pin "P$11") (pinfunction "P$11_P$11") (pintype "bidirectional"))
      (node (ref "VFD") (pin "P$29") (pinfunction "P$29_P$29") (pintype "bidirectional"))
    )
    (net (code "23") (name "HBU_P") (class "Default")
      (node (ref "HBU") (pin "P$10") (pinfunction "P$10_P$10") (pintype "bidirectional"))
      (node (ref "VFD") (pin "P$28") (pinfunction "P$28_P$28") (pintype "bidirectional"))
    )
    (net (code "24") (name "HBU_P1") (class "Default")
      (node (ref "DBR1") (pin "2") (pinfunction "2_2") (pintype "passive"))
      (node (ref "DBR2") (pin "2") (pinfunction "2_2") (pintype "passive"))
      (node (ref "HBU") (pin "P$8") (pinfunction "P$8_P$8") (pintype "bidirectional"))
    )
    (net (code "25") (name "HBU_P2") (class "Default")
      (node (ref "DBR1") (pin "1") (pinfunction "1_1") (pintype "passive"))
      (node (ref "DBR2") (pin "1") (pinfunction "1_1") (pintype "passive"))
      (node (ref "HBU") (pin "P$9") (pinfunction "P$9_P$9") (pintype "bidirectional"))
    )
    (net (code "26") (name "HBU_TB") (class "Default")
      (node (ref "HBU") (pin "P$5") (pinfunction "P$5_P$5") (pintype "bidirectional"))
    )
    (net (code "27") (name "HBU_TC") (class "Default")
      (node (ref "HBU") (pin "P$6") (pinfunction "P$6_P$6") (pintype "bidirectional"))
    )
    (net (code "28") (name "JOG_LEFT_SIGNAL") (class "Default")
      (node (ref "CPU1") (pin "P$J1-3") (pinfunction "J1_3_DIO19_P$J1-3") (pintype "bidirectional"))
      (node (ref "U$1") (pin "P$2") (pinfunction "LT_P$2") (pintype "bidirectional"))
    )
    (net (code "29") (name "JOG_RIGHT_SIGNAL") (class "Default")
      (node (ref "CPU1") (pin "P$J1-4") (pinfunction "J1_4_DIO17_P$J1-4") (pintype "bidirectional"))
      (node (ref "U$1") (pin "P$1") (pinfunction "LB_P$1") (pintype "bidirectional"))
    )
    (net (code "30") (name "JOYSTICK_FORWARD_SIGNAL") (class "Default")
      (node (ref "CPU1") (pin "P$J1-7") (pinfunction "J1_7_DIO20_P$J1-7") (pintype "bidirectional"))
      (node (ref "JOYSTICK") (pin "P$1") (pinfunction "A_P$1") (pintype "bidirectional"))
      (node (ref "U$16") (pin "P$1") (pinfunction "LB_P$1") (pintype "bidirectional"))
      (node (ref "U$16") (pin "P$3") (pinfunction "RB_P$3") (pintype "bidirectional"))
    )
    (net (code "31") (name "JOYSTICK_REVERSE_SIGNAL") (class "Default")
      (node (ref "CPU1") (pin "P$J1-8") (pinfunction "J1_8_DIO18_P$J1-8") (pintype "bidirectional"))
      (node (ref "JOYSTICK") (pin "P$2") (pinfunction "B_P$2") (pintype "bidirectional"))
      (node (ref "U$17") (pin "P$1") (pinfunction "LB_P$1") (pintype "bidirectional"))
      (node (ref "U$17") (pin "P$3") (pinfunction "RB_P$3") (pintype "bidirectional"))
    )
    (net (code "32") (name "JOYSTICK_SIGNAL") (class "Default")
      (node (ref "CPU1") (pin "P$J12-12") (pinfunction "J12_12_AIN0_P$J12-12") (pintype "bidirectional"))
      (node (ref "JOYSTICK") (pin "P$4") (pinfunction "SIG_P$4") (pintype "bidirectional"))
      (node (ref "U$16") (pin "P$2") (pinfunction "LT_P$2") (pintype "bidirectional"))
      (node (ref "U$16") (pin "P$4") (pinfunction "RT_P$4") (pintype "bidirectional"))
    )
    (net (code "33") (name "MAINS_L1") (class "Default")
      (node (ref "DS") (pin "P$3") (pinfunction "P$3_P$3") (pintype "bidirectional"))
      (node (ref "DS") (pin "P$4") (pinfunction "P$4_P$4") (pintype "bidirectional"))
      (node (ref "FUSE1") (pin "P$2") (pinfunction "P$2_P$2") (pintype "bidirectional"))
    )
    (net (code "34") (name "MAINS_L1_FUSED") (class "Default")
      (node (ref "CONT1") (pin "P$1") (pinfunction "1L1_P$1") (pintype "bidirectional"))
      (node (ref "CONT1") (pin "P$2") (pinfunction "2T1_P$2") (pintype "bidirectional"))
      (node (ref "FUSE1") (pin "P$3") (pinfunction "P$3_P$3") (pintype "bidirectional"))
      (node (ref "PS1") (pin "P$1") (pinfunction "1-AC/L_P$1") (pintype "bidirectional"))
      (node (ref "RELAY1") (pin "P$3") (pinfunction "14_P$3") (pintype "bidirectional"))
      (node (ref "RELAY2") (pin "P$3") (pinfunction "14_P$3") (pintype "bidirectional"))
      (node (ref "VFD") (pin "P$23") (pinfunction "P$23_P$23") (pintype "bidirectional"))
    )
    (net (code "35") (name "MAINS_L2") (class "Default")
      (node (ref "DS") (pin "P$2") (pinfunction "P$2_P$2") (pintype "bidirectional"))
      (node (ref "DS") (pin "P$5") (pinfunction "P$5_P$5") (pintype "bidirectional"))
      (node (ref "FUSE1") (pin "P$1") (pinfunction "P$1_P$1") (pintype "bidirectional"))
    )
    (net (code "36") (name "MAINS_L2_FUSED") (class "Default")
      (node (ref "CONT1") (pin "P$10") (pinfunction "A2_P$10") (pintype "bidirectional"))
      (node (ref "CONT1") (pin "P$3") (pinfunction "3L2_P$3") (pintype "bidirectional"))
      (node (ref "CONT1") (pin "P$4") (pinfunction "4T2_P$4") (pintype "bidirectional"))
      (node (ref "FUSE1") (pin "P$4") (pinfunction "P$4_P$4") (pintype "bidirectional"))
      (node (ref "PS1") (pin "P$2") (pinfunction "2-AC/N_P$2") (pintype "bidirectional"))
      (node (ref "U$6") (pin "P$1") (pinfunction "P$1_P$1") (pintype "bidirectional"))
      (node (ref "VFD") (pin "P$24") (pinfunction "P$24_P$24") (pintype "bidirectional"))
    )
    (net (code "37") (name "MAINS_L3") (class "Default")
      (node (ref "DS") (pin "P$1") (pinfunction "P$1_P$1") (pintype "bidirectional"))
      (node (ref "DS") (pin "P$6") (pinfunction "P$6_P$6") (pintype "bidirectional"))
      (node (ref "FUSE1") (pin "P$5") (pinfunction "P$5_P$5") (pintype "bidirectional"))
    )
    (net (code "38") (name "MAINS_L3_FUSED") (class "Default")
      (node (ref "CONT1") (pin "P$5") (pinfunction "5L3_P$5") (pintype "bidirectional"))
      (node (ref "CONT1") (pin "P$6") (pinfunction "6T3_P$6") (pintype "bidirectional"))
      (node (ref "FUSE1") (pin "P$6") (pinfunction "P$6_P$6") (pintype "bidirectional"))
      (node (ref "VFD") (pin "P$25") (pinfunction "P$25_P$25") (pintype "bidirectional"))
    )
    (net (code "39") (name "MAINS_PE") (class "Default")
      (node (ref "DS") (pin "P$7") (pinfunction "P$7_P$7") (pintype "bidirectional"))
      (node (ref "DS") (pin "P$8") (pinfunction "P$8_P$8") (pintype "bidirectional"))
    )
    (net (code "40") (name "MOTOR_PE") (class "Default")
      (node (ref "U$11") (pin "P$14") (pinfunction "GND_P$14") (pintype "bidirectional"))
    )
    (net (code "41") (name "MOTOR_U") (class "Default")
      (node (ref "U$11") (pin "P$11") (pinfunction "T7_P$11") (pintype "bidirectional"))
      (node (ref "U$11") (pin "P$5") (pinfunction "T1_P$5") (pintype "bidirectional"))
      (node (ref "VFD") (pin "P$32") (pinfunction "P$32_P$32") (pintype "bidirectional"))
    )
    (net (code "42") (name "MOTOR_V") (class "Default")
      (node (ref "U$11") (pin "P$12") (pinfunction "T8_P$12") (pintype "bidirectional"))
      (node (ref "U$11") (pin "P$6") (pinfunction "T2_P$6") (pintype "bidirectional"))
      (node (ref "VFD") (pin "P$31") (pinfunction "P$31_P$31") (pintype "bidirectional"))
    )
    (net (code "43") (name "MOTOR_W") (class "Default")
      (node (ref "U$11") (pin "P$13") (pinfunction "T9_P$13") (pintype "bidirectional"))
      (node (ref "U$11") (pin "P$7") (pinfunction "T3_P$7") (pintype "bidirectional"))
      (node (ref "VFD") (pin "P$30") (pinfunction "P$30_P$30") (pintype "bidirectional"))
    )
    (net (code "44") (name "Net-(U$8-LB)") (class "Default")
      (node (ref "R2") (pin "2") (pinfunction "2_2") (pintype "passive"))
      (node (ref "U$8") (pin "P$1") (pinfunction "LB_P$1") (pintype "bidirectional"))
    )
    (net (code "45") (name "Net-(U$8-LT)") (class "Default")
      (node (ref "R1") (pin "2") (pinfunction "2_2") (pintype "passive"))
      (node (ref "U$8") (pin "P$2") (pinfunction "LT_P$2") (pintype "bidirectional"))
    )
    (net (code "46") (name "Net-(U$11-T4)") (class "Default")
      (node (ref "U$11") (pin "P$10") (pinfunction "T6_P$10") (pintype "bidirectional"))
      (node (ref "U$11") (pin "P$8") (pinfunction "T4_P$8") (pintype "bidirectional"))
      (node (ref "U$11") (pin "P$9") (pinfunction "T5_P$9") (pintype "bidirectional"))
    )
    (net (code "47") (name "PE") (class "Default")
      (node (ref "PS1") (pin "P$3") (pinfunction "3-PE_P$3") (pintype "bidirectional"))
    )
    (net (code "48") (name "PROX_LEFT_SIGNAL") (class "Default")
      (node (ref "CPU1") (pin "P$J2-2") (pinfunction "J2_2_DIO29_P$J2-2") (pintype "bidirectional"))
      (node (ref "U$13") (pin "P$4") (pinfunction "SIG(BK)_P$4") (pintype "bidirectional"))
      (node (ref "U$24") (pin "P$1") (pinfunction "LB_P$1") (pintype "bidirectional"))
    )
    (net (code "49") (name "PROX_RIGHT_SIGNAL") (class "Default")
      (node (ref "CPU1") (pin "P$J2-1") (pinfunction "J2_1_DIO31_P$J2-1") (pintype "bidirectional"))
      (node (ref "U$12") (pin "P$4") (pinfunction "SIG(BK)_P$4") (pintype "bidirectional"))
      (node (ref "U$24") (pin "P$2") (pinfunction "LT_P$2") (pintype "bidirectional"))
    )
    (net (code "50") (name "RADIO_RS232_RX") (class "Default")
      (node (ref "CPU1") (pin "P$J11-7") (pinfunction "J11_7_PD3_RXF_P$J11-7") (pintype "bidirectional"))
      (node (ref "U$20") (pin "P$1") (pinfunction "LB_P$1") (pintype "bidirectional"))
    )
    (net (code "51") (name "RADIO_RS232_TX") (class "Default")
      (node (ref "CPU1") (pin "P$J11-2") (pinfunction "J11_2_PD2_TXF_P$J11-2") (pintype "bidirectional"))
      (node (ref "U$20") (pin "P$2") (pinfunction "LT_P$2") (pintype "bidirectional"))
    )
    (net (code "52") (name "REMOTE_SIGNAL") (class "Default")
      (node (ref "CPU1") (pin "P$J2-6") (pinfunction "J2_6_DIO30_P$J2-6") (pintype "bidirectional"))
      (node (ref "U$17") (pin "P$2") (pinfunction "LT_P$2") (pintype "bidirectional"))
    )
    (net (code "53") (name "RESET_SIGNAL") (class "Default")
      (node (ref "CPU1") (pin "P$J1-6") (pinfunction "J1_6_DIO22_P$J1-6") (pintype "bidirectional"))
      (node (ref "RESET") (pin "P$1") (pinfunction "P$1_P$1") (pintype "bidirectional"))
      (node (ref "U$18") (pin "P$2") (pinfunction "LT_P$2") (pintype "bidirectional"))
      (node (ref "U$18") (pin "P$4") (pinfunction "RT_P$4") (pintype "bidirectional"))
    )
    (net (code "54") (name "RS485+") (class "Default")
      (node (ref "U$21") (pin "P$4") (pinfunction "RT_P$4") (pintype "bidirectional"))
    )
    (net (code "55") (name "RS485-") (class "Default")
      (node (ref "U$21") (pin "P$3") (pinfunction "RB_P$3") (pintype "bidirectional"))
    )
    (net (code "56") (name "SPEED_SIGNAL") (class "Default")
      (node (ref "CPU1") (pin "P$J2-7") (pinfunction "J2_7_DIO28_P$J2-7") (pintype "bidirectional"))
      (node (ref "U$18") (pin "P$1") (pinfunction "LB_P$1") (pintype "bidirectional"))
    )
    (net (code "57") (name "STEPPER_DIR") (class "Default")
      (node (ref "CPU1") (pin "P$J4-4") (pinfunction "J4_4_HOUT7_P$J4-4") (pintype "bidirectional"))
      (node (ref "U$2") (pin "P$1") (pinfunction "LB_P$1") (pintype "bidirectional"))
    )
    (net (code "58") (name "STEPPER_STEP") (class "Default")
      (node (ref "CPU1") (pin "P$J4-1") (pinfunction "J4_1_HOUT5_P$J4-1") (pintype "bidirectional"))
      (node (ref "U$2") (pin "P$2") (pinfunction "LT_P$2") (pintype "bidirectional"))
    )
    (net (code "59") (name "THERMISTOR.SIGNAL") (class "Default")
      (node (ref "CPU1") (pin "P$J12-2") (pinfunction "J12_2_AIN6_P$J12-2") (pintype "bidirectional"))
      (node (ref "R2") (pin "1") (pinfunction "1_1") (pintype "passive"))
      (node (ref "U$14") (pin "P$1") (pinfunction "P$1_P$1") (pintype "bidirectional"))
      (node (ref "U$4") (pin "P$1") (pinfunction "LB_P$1") (pintype "bidirectional"))
      (node (ref "U$4") (pin "P$3") (pinfunction "RB_P$3") (pintype "bidirectional"))
    )
    (net (code "60") (name "USER_INPUT_1") (class "Default")
      (node (ref "CPU1") (pin "P$J10-1") (pinfunction "J10_1_DIO7_P$J10-1") (pintype "bidirectional"))
    )
    (net (code "61") (name "USER_INPUT_2") (class "Default")
      (node (ref "CPU1") (pin "P$J10-2") (pinfunction "J10_2_DIO5_P$J10-2") (pintype "bidirectional"))
    )
    (net (code "62") (name "USER_INPUT_3") (class "Default")
      (node (ref "CPU1") (pin "P$J10-3") (pinfunction "J10_3_DIO3_P$J10-3") (pintype "bidirectional"))
    )
    (net (code "63") (name "USER_INPUT_4") (class "Default")
      (node (ref "CPU1") (pin "P$J10-4") (pinfunction "J10_4_DIO1_P$J10-4") (pintype "bidirectional"))
    )
    (net (code "64") (name "USER_INPUT_5") (class "Default")
      (node (ref "CPU1") (pin "P$J10-6") (pinfunction "J10_6_DIO6_P$J10-6") (pintype "bidirectional"))
    )
    (net (code "65") (name "unconnected-(CONT1-13NO-PadP$7)") (class "Default")
      (node (ref "CONT1") (pin "P$7") (pinfunction "13NO_P$7") (pintype "bidirectional"))
    )
    (net (code "66") (name "unconnected-(CONT1-14N0-PadP$8)") (class "Default")
      (node (ref "CONT1") (pin "P$8") (pinfunction "14N0_P$8") (pintype "bidirectional"))
    )
    (net (code "67") (name "unconnected-(CPU1-J1_2_DIO21-PadP$J1-2)") (class "Default")
      (node (ref "CPU1") (pin "P$J1-2") (pinfunction "J1_2_DIO21_P$J1-2") (pintype "bidirectional"))
    )
    (net (code "68") (name "unconnected-(CPU1-J1_5_GND-PadP$J1-5)") (class "Default")
      (node (ref "CPU1") (pin "P$J1-5") (pinfunction "J1_5_GND_P$J1-5") (pintype "bidirectional"))
    )
    (net (code "69") (name "unconnected-(CPU1-J1_10_+KC-PadP$J1-10)") (class "Default")
      (node (ref "CPU1") (pin "P$J1-10") (pinfunction "J1_10_+KC_P$J1-10") (pintype "bidirectional"))
    )
    (net (code "70") (name "unconnected-(CPU1-J2_3_DIO27-PadP$J2-3)") (class "Default")
      (node (ref "CPU1") (pin "P$J2-3") (pinfunction "J2_3_DIO27_P$J2-3") (pintype "bidirectional"))
    )
    (net (code "71") (name "unconnected-(CPU1-J2_5_GND-PadP$J2-5)") (class "Default")
      (node (ref "CPU1") (pin "P$J2-5") (pinfunction "J2_5_GND_P$J2-5") (pintype "bidirectional"))
    )
    (net (code "72") (name "unconnected-(CPU1-J2_8_DIO26-PadP$J2-8)") (class "Default")
      (node (ref "CPU1") (pin "P$J2-8") (pinfunction "J2_8_DIO26_P$J2-8") (pintype "bidirectional"))
    )
    (net (code "73") (name "unconnected-(CPU1-J2_9_DIO24-PadP$J2-9)") (class "Default")
      (node (ref "CPU1") (pin "P$J2-9") (pinfunction "J2_9_DIO24_P$J2-9") (pintype "bidirectional"))
    )
    (net (code "74") (name "unconnected-(CPU1-J2_10_+KD-PadP$J2-10)") (class "Default")
      (node (ref "CPU1") (pin "P$J2-10") (pinfunction "J2_10_+KD_P$J2-10") (pintype "bidirectional"))
    )
    (net (code "75") (name "unconnected-(CPU1-J3_2_GND-PadP$J3-2)") (class "Default")
      (node (ref "CPU1") (pin "P$J3-2") (pinfunction "J3_2_GND_P$J3-2") (pintype "bidirectional"))
    )
    (net (code "76") (name "unconnected-(CPU1-J3_6_HOUT0-PadP$J3-6)") (class "Default")
      (node (ref "CPU1") (pin "P$J3-6") (pinfunction "J3_6_HOUT0_P$J3-6") (pintype "bidirectional"))
    )
    (net (code "77") (name "unconnected-(CPU1-J3_7_+K1-PadP$J3-7)") (class "Default")
      (node (ref "CPU1") (pin "P$J3-7") (pinfunction "J3_7_+K1_P$J3-7") (pintype "bidirectional"))
    )
    (net (code "78") (name "unconnected-(CPU1-J3_9_HOUT2-PadP$J3-9)") (class "Default")
      (node (ref "CPU1") (pin "P$J3-9") (pinfunction "J3_9_HOUT2_P$J3-9") (pintype "bidirectional"))
    )
    (net (code "79") (name "unconnected-(CPU1-J4_2_GND-PadP$J4-2)") (class "Default")
      (node (ref "CPU1") (pin "P$J4-2") (pinfunction "J4_2_GND_P$J4-2") (pintype "bidirectional"))
    )
    (net (code "80") (name "unconnected-(CPU1-J4_5_GND-PadP$J4-5)") (class "Default")
      (node (ref "CPU1") (pin "P$J4-5") (pinfunction "J4_5_GND_P$J4-5") (pintype "bidirectional"))
    )
    (net (code "81") (name "unconnected-(CPU1-J4_6_HOUT4-PadP$J4-6)") (class "Default")
      (node (ref "CPU1") (pin "P$J4-6") (pinfunction "J4_6_HOUT4_P$J4-6") (pintype "bidirectional"))
    )
    (net (code "82") (name "unconnected-(CPU1-J4_7_+K2-PadP$J4-7)") (class "Default")
      (node (ref "CPU1") (pin "P$J4-7") (pinfunction "J4_7_+K2_P$J4-7") (pintype "bidirectional"))
    )
    (net (code "83") (name "unconnected-(CPU1-J4_9_HOUT6-PadP$J4-9)") (class "Default")
      (node (ref "CPU1") (pin "P$J4-9") (pinfunction "J4_9_HOUT6_P$J4-9") (pintype "bidirectional"))
    )
    (net (code "84") (name "unconnected-(CPU1-J7_1_+RAW-PadP$J7-1)") (class "Default")
      (node (ref "CPU1") (pin "P$J7-1") (pinfunction "J7_1_+RAW_P$J7-1") (pintype "bidirectional"))
    )
    (net (code "85") (name "unconnected-(CPU1-J7_2_+RAW-PadP$J7-2)") (class "Default")
      (node (ref "CPU1") (pin "P$J7-2") (pinfunction "J7_2_+RAW_P$J7-2") (pintype "bidirectional"))
    )
    (net (code "86") (name "unconnected-(CPU1-J7_3_+5V-PadP$J7-3)") (class "Default")
      (node (ref "CPU1") (pin "P$J7-3") (pinfunction "J7_3_+5V_P$J7-3") (pintype "bidirectional"))
    )
    (net (code "87") (name "unconnected-(CPU1-J7_4_GND-PadP$J7-4)") (class "Default")
      (node (ref "CPU1") (pin "P$J7-4") (pinfunction "J7_4_GND_P$J7-4") (pintype "bidirectional"))
    )
    (net (code "88") (name "unconnected-(CPU1-J7_5_GND-PadP$J7-5)") (class "Default")
      (node (ref "CPU1") (pin "P$J7-5") (pinfunction "J7_5_GND_P$J7-5") (pintype "bidirectional"))
    )
    (net (code "89") (name "unconnected-(CPU1-J7_6_+5V-PadP$J7-6)") (class "Default")
      (node (ref "CPU1") (pin "P$J7-6") (pinfunction "J7_6_+5V_P$J7-6") (pintype "bidirectional"))
    )
    (net (code "90") (name "unconnected-(CPU1-J9_1_DIO15-PadP$J9-1)") (class "Default")
      (node (ref "CPU1") (pin "P$J9-1") (pinfunction "J9_1_DIO15_P$J9-1") (pintype "bidirectional"))
    )
    (net (code "91") (name "unconnected-(CPU1-J9_2_DIO13-PadP$J9-2)") (class "Default")
      (node (ref "CPU1") (pin "P$J9-2") (pinfunction "J9_2_DIO13_P$J9-2") (pintype "bidirectional"))
    )
    (net (code "92") (name "unconnected-(CPU1-J9_3_DIO11-PadP$J9-3)") (class "Default")
      (node (ref "CPU1") (pin "P$J9-3") (pinfunction "J9_3_DIO11_P$J9-3") (pintype "bidirectional"))
    )
    (net (code "93") (name "unconnected-(CPU1-J9_4_DIO9-PadP$J9-4)") (class "Default")
      (node (ref "CPU1") (pin "P$J9-4") (pinfunction "J9_4_DIO9_P$J9-4") (pintype "bidirectional"))
    )
    (net (code "94") (name "unconnected-(CPU1-J9_5_GND-PadP$J9-5)") (class "Default")
      (node (ref "CPU1") (pin "P$J9-5") (pinfunction "J9_5_GND_P$J9-5") (pintype "bidirectional"))
    )
    (net (code "95") (name "unconnected-(CPU1-J9_6_DIO14-PadP$J9-6)") (class "Default")
      (node (ref "CPU1") (pin "P$J9-6") (pinfunction "J9_6_DIO14_P$J9-6") (pintype "bidirectional"))
    )
    (net (code "96") (name "unconnected-(CPU1-J9_7_DIO12-PadP$J9-7)") (class "Default")
      (node (ref "CPU1") (pin "P$J9-7") (pinfunction "J9_7_DIO12_P$J9-7") (pintype "bidirectional"))
    )
    (net (code "97") (name "unconnected-(CPU1-J9_8_DIO10-PadP$J9-8)") (class "Default")
      (node (ref "CPU1") (pin "P$J9-8") (pinfunction "J9_8_DIO10_P$J9-8") (pintype "bidirectional"))
    )
    (net (code "98") (name "unconnected-(CPU1-J9_9_DIO8-PadP$J9-9)") (class "Default")
      (node (ref "CPU1") (pin "P$J9-9") (pinfunction "J9_9_DIO8_P$J9-9") (pintype "bidirectional"))
    )
    (net (code "99") (name "unconnected-(CPU1-J9_10_+KB-PadP$J9-10)") (class "Default")
      (node (ref "CPU1") (pin "P$J9-10") (pinfunction "J9_10_+KB_P$J9-10") (pintype "bidirectional"))
    )
    (net (code "100") (name "unconnected-(CPU1-J10_5_GND-PadP$J10-5)") (class "Default")
      (node (ref "CPU1") (pin "P$J10-5") (pinfunction "J10_5_GND_P$J10-5") (pintype "bidirectional"))
    )
    (net (code "101") (name "unconnected-(CPU1-J10_7_DIO4-PadP$J10-7)") (class "Default")
      (node (ref "CPU1") (pin "P$J10-7") (pinfunction "J10_7_DIO4_P$J10-7") (pintype "bidirectional"))
    )
    (net (code "102") (name "unconnected-(CPU1-J10_8_DIO2-PadP$J10-8)") (class "Default")
      (node (ref "CPU1") (pin "P$J10-8") (pinfunction "J10_8_DIO2_P$J10-8") (pintype "bidirectional"))
    )
    (net (code "103") (name "unconnected-(CPU1-J10_9_DIO0-PadP$J10-9)") (class "Default")
      (node (ref "CPU1") (pin "P$J10-9") (pinfunction "J10_9_DIO0_P$J10-9") (pintype "bidirectional"))
    )
    (net (code "104") (name "unconnected-(CPU1-J10_10_+KA-PadP$J10-10)") (class "Default")
      (node (ref "CPU1") (pin "P$J10-10") (pinfunction "J10_10_+KA_P$J10-10") (pintype "bidirectional"))
    )
    (net (code "105") (name "unconnected-(CPU1-J11_3_GND-PadP$J11-3)") (class "Default")
      (node (ref "CPU1") (pin "P$J11-3") (pinfunction "J11_3_GND_P$J11-3") (pintype "bidirectional"))
    )
    (net (code "106") (name "unconnected-(CPU1-J11_5_GND-PadP$J11-5)") (class "Default")
      (node (ref "CPU1") (pin "P$J11-5") (pinfunction "J11_5_GND_P$J11-5") (pintype "bidirectional"))
    )
    (net (code "107") (name "unconnected-(CPU1-J11_6_PD7_RXE-PadP$J11-6)") (class "Default")
      (node (ref "CPU1") (pin "P$J11-6") (pinfunction "J11_6_PD7_RXE_P$J11-6") (pintype "bidirectional"))
    )
    (net (code "108") (name "unconnected-(CPU1-J11_8_GND-PadP$J11-8)") (class "Default")
      (node (ref "CPU1") (pin "P$J11-8") (pinfunction "J11_8_GND_P$J11-8") (pintype "bidirectional"))
    )
    (net (code "109") (name "unconnected-(CPU1-J12_3_AIN4-PadP$J12-3)") (class "Default")
      (node (ref "CPU1") (pin "P$J12-3") (pinfunction "J12_3_AIN4_P$J12-3") (pintype "bidirectional"))
    )
    (net (code "110") (name "unconnected-(CPU1-J12_4_AIN3-PadP$J12-4)") (class "Default")
      (node (ref "CPU1") (pin "P$J12-4") (pinfunction "J12_4_AIN3_P$J12-4") (pintype "bidirectional"))
    )
    (net (code "111") (name "unconnected-(CPU1-J12_5_AIN1-PadP$J12-5)") (class "Default")
      (node (ref "CPU1") (pin "P$J12-5") (pinfunction "J12_5_AIN1_P$J12-5") (pintype "bidirectional"))
    )
    (net (code "112") (name "unconnected-(CPU1-J12_6_AGND-PadP$J12-6)") (class "Default")
      (node (ref "CPU1") (pin "P$J12-6") (pinfunction "J12_6_AGND_P$J12-6") (pintype "bidirectional"))
    )
    (net (code "113") (name "unconnected-(CPU1-J12_7_AOUT1-PadP$J12-7)") (class "Default")
      (node (ref "CPU1") (pin "P$J12-7") (pinfunction "J12_7_AOUT1_P$J12-7") (pintype "bidirectional"))
    )
    (net (code "114") (name "unconnected-(CPU1-J12_8_AIN7-PadP$J12-8)") (class "Default")
      (node (ref "CPU1") (pin "P$J12-8") (pinfunction "J12_8_AIN7_P$J12-8") (pintype "bidirectional"))
    )
    (net (code "115") (name "unconnected-(CPU1-J12_9_AIN5-PadP$J12-9)") (class "Default")
      (node (ref "CPU1") (pin "P$J12-9") (pinfunction "J12_9_AIN5_P$J12-9") (pintype "bidirectional"))
    )
    (net (code "116") (name "unconnected-(CPU1-J12_10_AGND-PadP$J12-10)") (class "Default")
      (node (ref "CPU1") (pin "P$J12-10") (pinfunction "J12_10_AGND_P$J12-10") (pintype "bidirectional"))
    )
    (net (code "117") (name "unconnected-(CPU1-J12_11_AIN2-PadP$J12-11)") (class "Default")
      (node (ref "CPU1") (pin "P$J12-11") (pinfunction "J12_11_AIN2_P$J12-11") (pintype "bidirectional"))
    )
    (net (code "118") (name "unconnected-(CPU1-J12_14_AGND-PadP$J12-14)") (class "Default")
      (node (ref "CPU1") (pin "P$J12-14") (pinfunction "J12_14_AGND_P$J12-14") (pintype "bidirectional"))
    )
    (net (code "119") (name "unconnected-(HBU-PadP$1)") (class "Default")
      (node (ref "HBU") (pin "P$1") (pinfunction "P$1_P$1") (pintype "bidirectional"))
    )
    (net (code "120") (name "unconnected-(HBU-PadP$2)") (class "Default")
      (node (ref "HBU") (pin "P$2") (pinfunction "P$2_P$2") (pintype "bidirectional"))
    )
    (net (code "121") (name "unconnected-(HBU-PadP$3)") (class "Default")
      (node (ref "HBU") (pin "P$3") (pinfunction "P$3_P$3") (pintype "bidirectional"))
    )
    (net (code "122") (name "unconnected-(HBU-PadP$4)") (class "Default")
      (node (ref "HBU") (pin "P$4") (pinfunction "P$4_P$4") (pintype "bidirectional"))
    )
    (net (code "123") (name "unconnected-(PS2-+5VDCB-PadP$2)") (class "Default")
      (node (ref "PS2") (pin "P$2") (pinfunction "+5VDCB_P$2") (pintype "bidirectional"))
    )
    (net (code "124") (name "unconnected-(RELAY1-12-PadP$2)") (class "Default")
      (node (ref "RELAY1") (pin "P$2") (pinfunction "12_P$2") (pintype "bidirectional"))
    )
    (net (code "125") (name "unconnected-(RELAY2-12-PadP$2)") (class "Default")
      (node (ref "RELAY2") (pin "P$2") (pinfunction "12_P$2") (pintype "bidirectional"))
    )
    (net (code "126") (name "unconnected-(U$1-RB-PadP$3)") (class "Default")
      (node (ref "U$1") (pin "P$3") (pinfunction "RB_P$3") (pintype "bidirectional"))
    )
    (net (code "127") (name "unconnected-(U$1-RT-PadP$4)") (class "Default")
      (node (ref "U$1") (pin "P$4") (pinfunction "RT_P$4") (pintype "bidirectional"))
    )
    (net (code "128") (name "unconnected-(U$2-RB-PadP$3)") (class "Default")
      (node (ref "U$2") (pin "P$3") (pinfunction "RB_P$3") (pintype "bidirectional"))
    )
    (net (code "129") (name "unconnected-(U$2-RT-PadP$4)") (class "Default")
      (node (ref "U$2") (pin "P$4") (pinfunction "RT_P$4") (pintype "bidirectional"))
    )
    (net (code "130") (name "unconnected-(U$5-1-PadP$1)") (class "Default")
      (node (ref "U$5") (pin "P$1") (pinfunction "1_P$1") (pintype "bidirectional"))
    )
    (net (code "131") (name "unconnected-(U$5-2-PadP$2)") (class "Default")
      (node (ref "U$5") (pin "P$2") (pinfunction "2_P$2") (pintype "bidirectional"))
    )
    (net (code "132") (name "unconnected-(U$5-3-PadP$3)") (class "Default")
      (node (ref "U$5") (pin "P$3") (pinfunction "3_P$3") (pintype "bidirectional"))
    )
    (net (code "133") (name "unconnected-(U$5-4-PadP$4)") (class "Default")
      (node (ref "U$5") (pin "P$4") (pinfunction "4_P$4") (pintype "bidirectional"))
    )
    (net (code "134") (name "unconnected-(U$5-5-PadP$5)") (class "Default")
      (node (ref "U$5") (pin "P$5") (pinfunction "5_P$5") (pintype "bidirectional"))
    )
    (net (code "135") (name "unconnected-(U$5-6-PadP$6)") (class "Default")
      (node (ref "U$5") (pin "P$6") (pinfunction "6_P$6") (pintype "bidirectional"))
    )
    (net (code "136") (name "unconnected-(U$5-7-PadP$7)") (class "Default")
      (node (ref "U$5") (pin "P$7") (pinfunction "7_P$7") (pintype "bidirectional"))
    )
    (net (code "137") (name "unconnected-(U$5-8-PadP$8)") (class "Default")
      (node (ref "U$5") (pin "P$8") (pinfunction "8_P$8") (pintype "bidirectional"))
    )
    (net (code "138") (name "unconnected-(U$5-9-PadP$9)") (class "Default")
      (node (ref "U$5") (pin "P$9") (pinfunction "9_P$9") (pintype "bidirectional"))
    )
    (net (code "139") (name "unconnected-(U$7-LB-PadP$1)") (class "Default")
      (node (ref "U$7") (pin "P$1") (pinfunction "LB_P$1") (pintype "bidirectional"))
    )
    (net (code "140") (name "unconnected-(U$7-LT-PadP$2)") (class "Default")
      (node (ref "U$7") (pin "P$2") (pinfunction "LT_P$2") (pintype "bidirectional"))
    )
    (net (code "141") (name "unconnected-(U$7-RB-PadP$3)") (class "Default")
      (node (ref "U$7") (pin "P$3") (pinfunction "RB_P$3") (pintype "bidirectional"))
    )
    (net (code "142") (name "unconnected-(U$7-RT-PadP$4)") (class "Default")
      (node (ref "U$7") (pin "P$4") (pinfunction "RT_P$4") (pintype "bidirectional"))
    )
    (net (code "143") (name "unconnected-(U$9-PadP$1)") (class "Default")
      (node (ref "U$9") (pin "P$1") (pinfunction "P$1_P$1") (pintype "bidirectional"))
    )
    (net (code "144") (name "unconnected-(U$9-PadP$3)") (class "Default")
      (node (ref "U$9") (pin "P$3") (pinfunction "P$3_P$3") (pintype "bidirectional"))
    )
    (net (code "145") (name "unconnected-(U$10-PadP$1)") (class "Default")
      (node (ref "U$10") (pin "P$1") (pinfunction "P$1_P$1") (pintype "bidirectional"))
    )
    (net (code "146") (name "unconnected-(U$10-PadP$3)") (class "Default")
      (node (ref "U$10") (pin "P$3") (pinfunction "P$3_P$3") (pintype "bidirectional"))
    )
    (net (code "147") (name "unconnected-(U$12-CHASSIS{slash}SHIELD-PadP$1)") (class "Default")
      (node (ref "U$12") (pin "P$1") (pinfunction "CHASSIS/SHIELD_P$1") (pintype "bidirectional"))
    )
    (net (code "148") (name "unconnected-(U$13-CHASSIS{slash}SHIELD-PadP$1)") (class "Default")
      (node (ref "U$13") (pin "P$1") (pinfunction "CHASSIS/SHIELD_P$1") (pintype "bidirectional"))
    )
    (net (code "149") (name "unconnected-(U$17-RT-PadP$4)") (class "Default")
      (node (ref "U$17") (pin "P$4") (pinfunction "RT_P$4") (pintype "bidirectional"))
    )
    (net (code "150") (name "unconnected-(U$18-RB-PadP$3)") (class "Default")
      (node (ref "U$18") (pin "P$3") (pinfunction "RB_P$3") (pintype "bidirectional"))
    )
    (net (code "151") (name "unconnected-(U$19-LB-PadP$1)") (class "Default")
      (node (ref "U$19") (pin "P$1") (pinfunction "LB_P$1") (pintype "bidirectional"))
    )
    (net (code "152") (name "unconnected-(U$19-RB-PadP$3)") (class "Default")
      (node (ref "U$19") (pin "P$3") (pinfunction "RB_P$3") (pintype "bidirectional"))
    )
    (net (code "153") (name "unconnected-(U$20-RB-PadP$3)") (class "Default")
      (node (ref "U$20") (pin "P$3") (pinfunction "RB_P$3") (pintype "bidirectional"))
    )
    (net (code "154") (name "unconnected-(U$20-RT-PadP$4)") (class "Default")
      (node (ref "U$20") (pin "P$4") (pinfunction "RT_P$4") (pintype "bidirectional"))
    )
    (net (code "155") (name "unconnected-(U$24-RB-PadP$3)") (class "Default")
      (node (ref "U$24") (pin "P$3") (pinfunction "RB_P$3") (pintype "bidirectional"))
    )
    (net (code "156") (name "unconnected-(U$24-RT-PadP$4)") (class "Default")
      (node (ref "U$24") (pin "P$4") (pinfunction "RT_P$4") (pintype "bidirectional"))
    )
    (net (code "157") (name "unconnected-(U$25-LB-PadP$1)") (class "Default")
      (node (ref "U$25") (pin "P$1") (pinfunction "LB_P$1") (pintype "bidirectional"))
    )
    (net (code "158") (name "unconnected-(U$25-RB-PadP$3)") (class "Default")
      (node (ref "U$25") (pin "P$3") (pinfunction "RB_P$3") (pintype "bidirectional"))
    )
    (net (code "159") (name "unconnected-(U$26-LB-PadP$1)") (class "Default")
      (node (ref "U$26") (pin "P$1") (pinfunction "LB_P$1") (pintype "bidirectional"))
    )
    (net (code "160") (name "unconnected-(U$26-LT-PadP$2)") (class "Default")
      (node (ref "U$26") (pin "P$2") (pinfunction "LT_P$2") (pintype "bidirectional"))
    )
    (net (code "161") (name "unconnected-(U$26-RT-PadP$4)") (class "Default")
      (node (ref "U$26") (pin "P$4") (pinfunction "RT_P$4") (pintype "bidirectional"))
    )
    (net (code "162") (name "unconnected-(U$28-RB-PadP$3)") (class "Default")
      (node (ref "U$28") (pin "P$3") (pinfunction "RB_P$3") (pintype "bidirectional"))
    )
    (net (code "163") (name "unconnected-(U$28-RT-PadP$4)") (class "Default")
      (node (ref "U$28") (pin "P$4") (pinfunction "RT_P$4") (pintype "bidirectional"))
    )
    (net (code "164") (name "unconnected-(U$29-LB-PadP$1)") (class "Default")
      (node (ref "U$29") (pin "P$1") (pinfunction "LB_P$1") (pintype "bidirectional"))
    )
    (net (code "165") (name "unconnected-(U$29-LT-PadP$2)") (class "Default")
      (node (ref "U$29") (pin "P$2") (pinfunction "LT_P$2") (pintype "bidirectional"))
    )
    (net (code "166") (name "unconnected-(U$29-RT-PadP$4)") (class "Default")
      (node (ref "U$29") (pin "P$4") (pinfunction "RT_P$4") (pintype "bidirectional"))
    )
    (net (code "167") (name "unconnected-(U$30-LB-PadP$1)") (class "Default")
      (node (ref "U$30") (pin "P$1") (pinfunction "LB_P$1") (pintype "bidirectional"))
    )
    (net (code "168") (name "unconnected-(U$30-LT-PadP$2)") (class "Default")
      (node (ref "U$30") (pin "P$2") (pinfunction "LT_P$2") (pintype "bidirectional"))
    )
    (net (code "169") (name "unconnected-(U$30-RB-PadP$3)") (class "Default")
      (node (ref "U$30") (pin "P$3") (pinfunction "RB_P$3") (pintype "bidirectional"))
    )
    (net (code "170") (name "unconnected-(U$30-RT-PadP$4)") (class "Default")
      (node (ref "U$30") (pin "P$4") (pinfunction "RT_P$4") (pintype "bidirectional"))
    )
    (net (code "171") (name "unconnected-(U$33-LB-PadP$1)") (class "Default")
      (node (ref "U$33") (pin "P$1") (pinfunction "LB_P$1") (pintype "bidirectional"))
    )
    (net (code "172") (name "unconnected-(U$34-RB-PadP$3)") (class "Default")
      (node (ref "U$34") (pin "P$3") (pinfunction "RB_P$3") (pintype "bidirectional"))
    )
    (net (code "173") (name "unconnected-(U$34-RT-PadP$4)") (class "Default")
      (node (ref "U$34") (pin "P$4") (pinfunction "RT_P$4") (pintype "bidirectional"))
    )
    (net (code "174") (name "unconnected-(U$35-RB-PadP$3)") (class "Default")
      (node (ref "U$35") (pin "P$3") (pinfunction "RB_P$3") (pintype "bidirectional"))
    )
    (net (code "175") (name "unconnected-(VFD-PadP$1)") (class "Default")
      (node (ref "VFD") (pin "P$1") (pinfunction "P$1_P$1") (pintype "bidirectional"))
    )
    (net (code "176") (name "unconnected-(VFD-PadP$2)") (class "Default")
      (node (ref "VFD") (pin "P$2") (pinfunction "P$2_P$2") (pintype "bidirectional"))
    )
    (net (code "177") (name "unconnected-(VFD-PadP$3)") (class "Default")
      (node (ref "VFD") (pin "P$3") (pinfunction "P$3_P$3") (pintype "bidirectional"))
    )
    (net (code "178") (name "unconnected-(VFD-PadP$4)") (class "Default")
      (node (ref "VFD") (pin "P$4") (pinfunction "P$4_P$4") (pintype "bidirectional"))
    )
    (net (code "179") (name "unconnected-(VFD-PadP$5)") (class "Default")
      (node (ref "VFD") (pin "P$5") (pinfunction "P$5_P$5") (pintype "bidirectional"))
    )
    (net (code "180") (name "unconnected-(VFD-PadP$6)") (class "Default")
      (node (ref "VFD") (pin "P$6") (pinfunction "P$6_P$6") (pintype "bidirectional"))
    )
    (net (code "181") (name "unconnected-(VFD-PadP$7)") (class "Default")
      (node (ref "VFD") (pin "P$7") (pinfunction "P$7_P$7") (pintype "bidirectional"))
    )
    (net (code "182") (name "unconnected-(VFD-PadP$8)") (class "Default")
      (node (ref "VFD") (pin "P$8") (pinfunction "P$8_P$8") (pintype "bidirectional"))
    )
    (net (code "183") (name "unconnected-(VFD-PadP$9)") (class "Default")
      (node (ref "VFD") (pin "P$9") (pinfunction "P$9_P$9") (pintype "bidirectional"))
    )
    (net (code "184") (name "unconnected-(VFD-PadP$10)") (class "Default")
      (node (ref "VFD") (pin "P$10") (pinfunction "P$10_P$10") (pintype "bidirectional"))
    )
    (net (code "185") (name "unconnected-(VFD-PadP$11)") (class "Default")
      (node (ref "VFD") (pin "P$11") (pinfunction "P$11_P$11") (pintype "bidirectional"))
    )
    (net (code "186") (name "unconnected-(VFD-PadP$12)") (class "Default")
      (node (ref "VFD") (pin "P$12") (pinfunction "P$12_P$12") (pintype "bidirectional"))
    )
    (net (code "187") (name "unconnected-(VFD-PadP$13)") (class "Default")
      (node (ref "VFD") (pin "P$13") (pinfunction "P$13_P$13") (pintype "bidirectional"))
    )
    (net (code "188") (name "unconnected-(VFD-PadP$14)") (class "Default")
      (node (ref "VFD") (pin "P$14") (pinfunction "P$14_P$14") (pintype "bidirectional"))
    )
    (net (code "189") (name "unconnected-(VFD-PadP$15)") (class "Default")
      (node (ref "VFD") (pin "P$15") (pinfunction "P$15_P$15") (pintype "bidirectional"))
    )
    (net (code "190") (name "unconnected-(VFD-PadP$16)") (class "Default")
      (node (ref "VFD") (pin "P$16") (pinfunction "P$16_P$16") (pintype "bidirectional"))
    )
    (net (code "191") (name "unconnected-(VFD-PadP$17)") (class "Default")
      (node (ref "VFD") (pin "P$17") (pinfunction "P$17_P$17") (pintype "bidirectional"))
    )
    (net (code "192") (name "unconnected-(VFD-PadP$18)") (class "Default")
      (node (ref "VFD") (pin "P$18") (pinfunction "P$18_P$18") (pintype "bidirectional"))
    )
    (net (code "193") (name "unconnected-(VFD-PadP$19)") (class "Default")
      (node (ref "VFD") (pin "P$19") (pinfunction "P$19_P$19") (pintype "bidirectional"))
    )
    (net (code "194") (name "unconnected-(VFD-PadP$20)") (class "Default")
      (node (ref "VFD") (pin "P$20") (pinfunction "P$20_P$20") (pintype "bidirectional"))
    )
    (net (code "195") (name "unconnected-(VFD-PadP$21)") (class "Default")
      (node (ref "VFD") (pin "P$21") (pinfunction "P$21_P$21") (pintype "bidirectional"))
    )
    (net (code "196") (name "unconnected-(VFD-PadP$22)") (class "Default")
      (node (ref "VFD") (pin "P$22") (pinfunction "P$22_P$22") (pintype "bidirectional"))
    )
    (net (code "197") (name "unconnected-(VFD-PadP$26)") (class "Default")
      (node (ref "VFD") (pin "P$26") (pinfunction "P$26_P$26") (pintype "bidirectional"))
    )
    (net (code "198") (name "unconnected-(VFD-PadP$27)") (class "Default")
      (node (ref "VFD") (pin "P$27") (pinfunction "P$27_P$27") (pintype "bidirectional"))
    )
    (net (code "199") (name "unconnected-(VFD-PadP$33)") (class "Default")
      (node (ref "VFD") (pin "P$33") (pinfunction "P$33_P$33") (pintype "bidirectional"))
    )
    (net (code "200") (name "unconnected-(VFD-PadP$34)") (class "Default")
      (node (ref "VFD") (pin "P$34") (pinfunction "P$34_P$34") (pintype "bidirectional"))
    )
  )
)
